# Ddraig.net
KiCad netlist of a schematic drawn in EAGLE
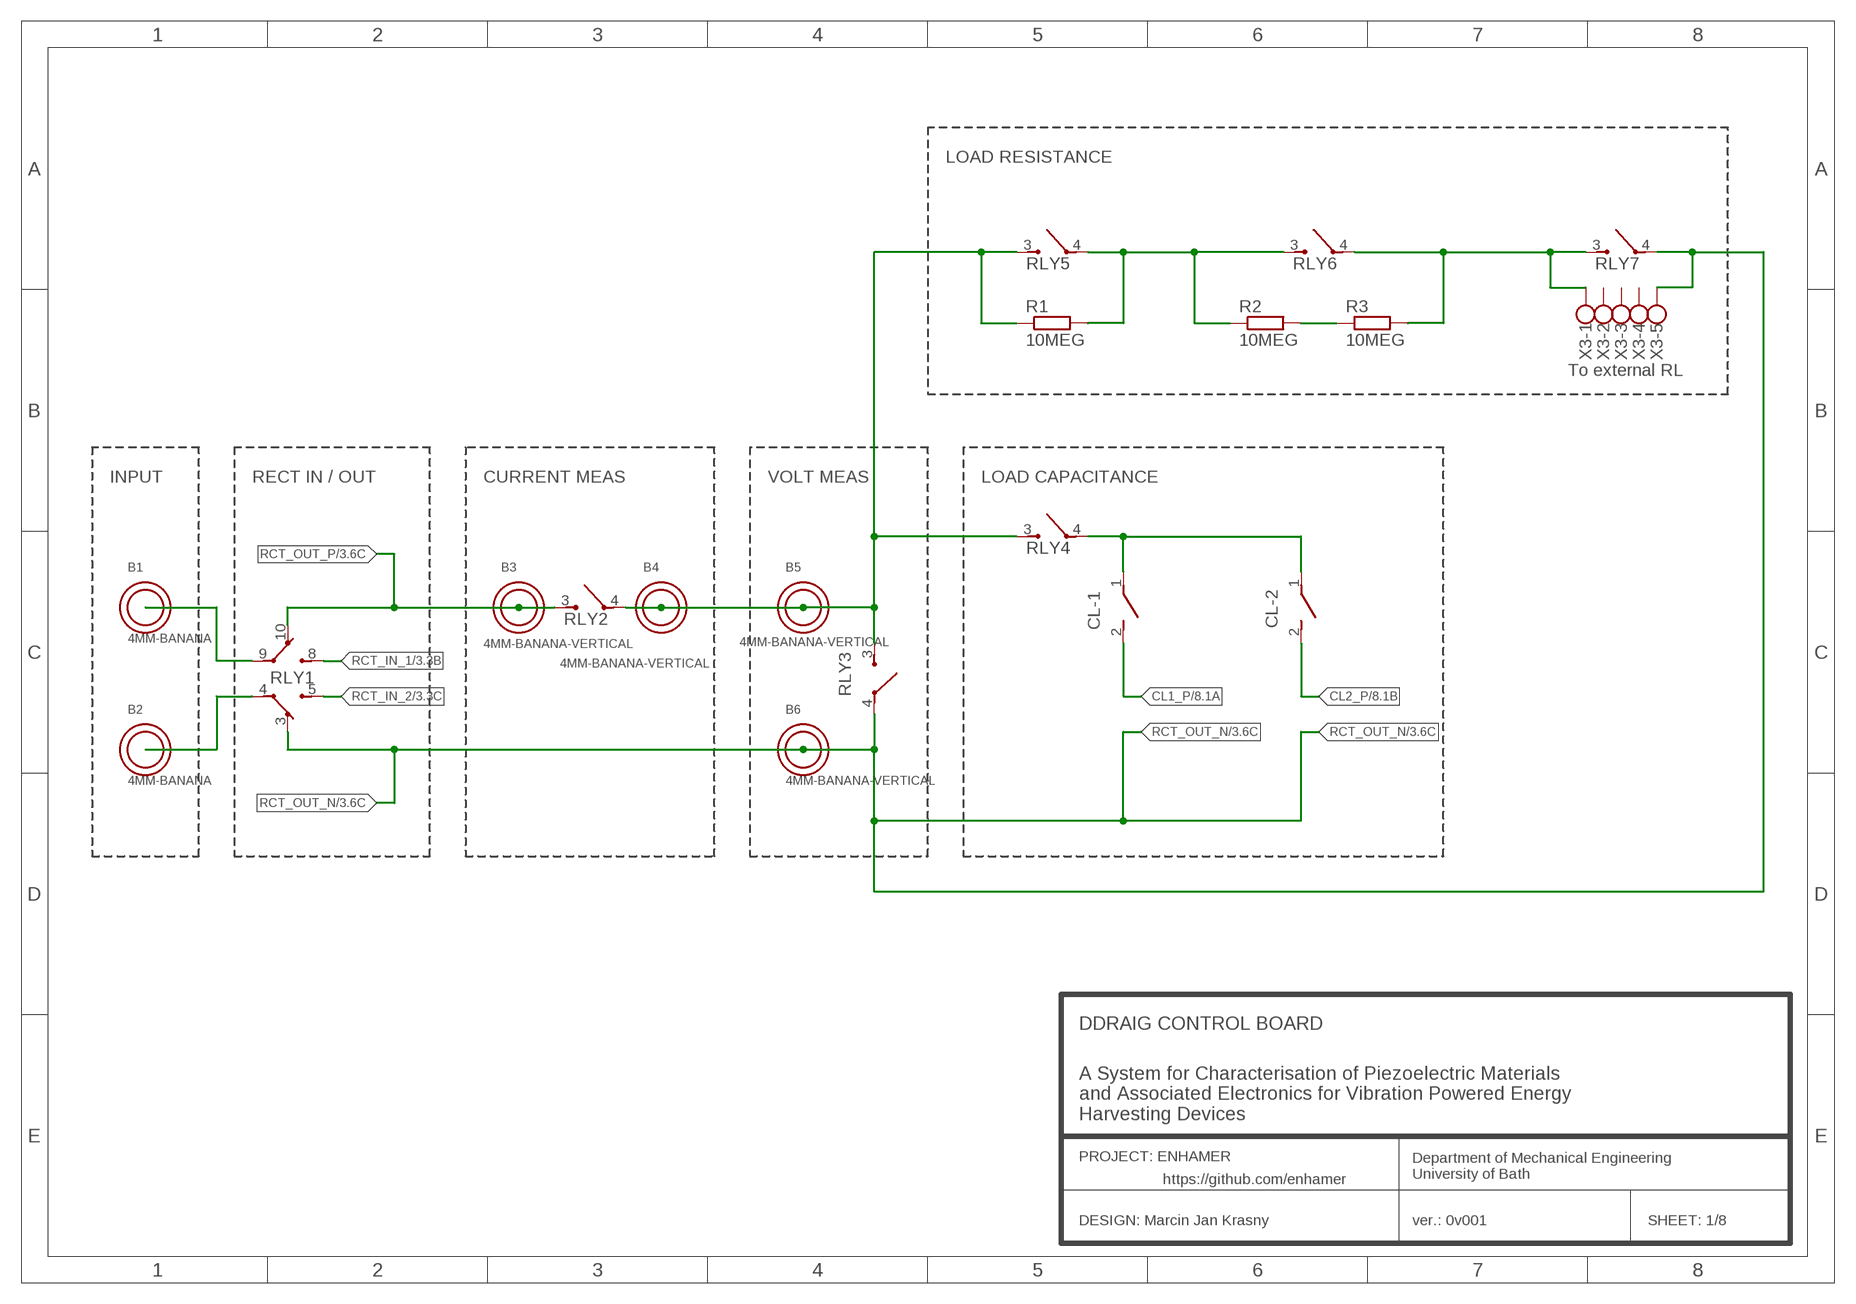
[diagram p0: schematic, sheet 1]
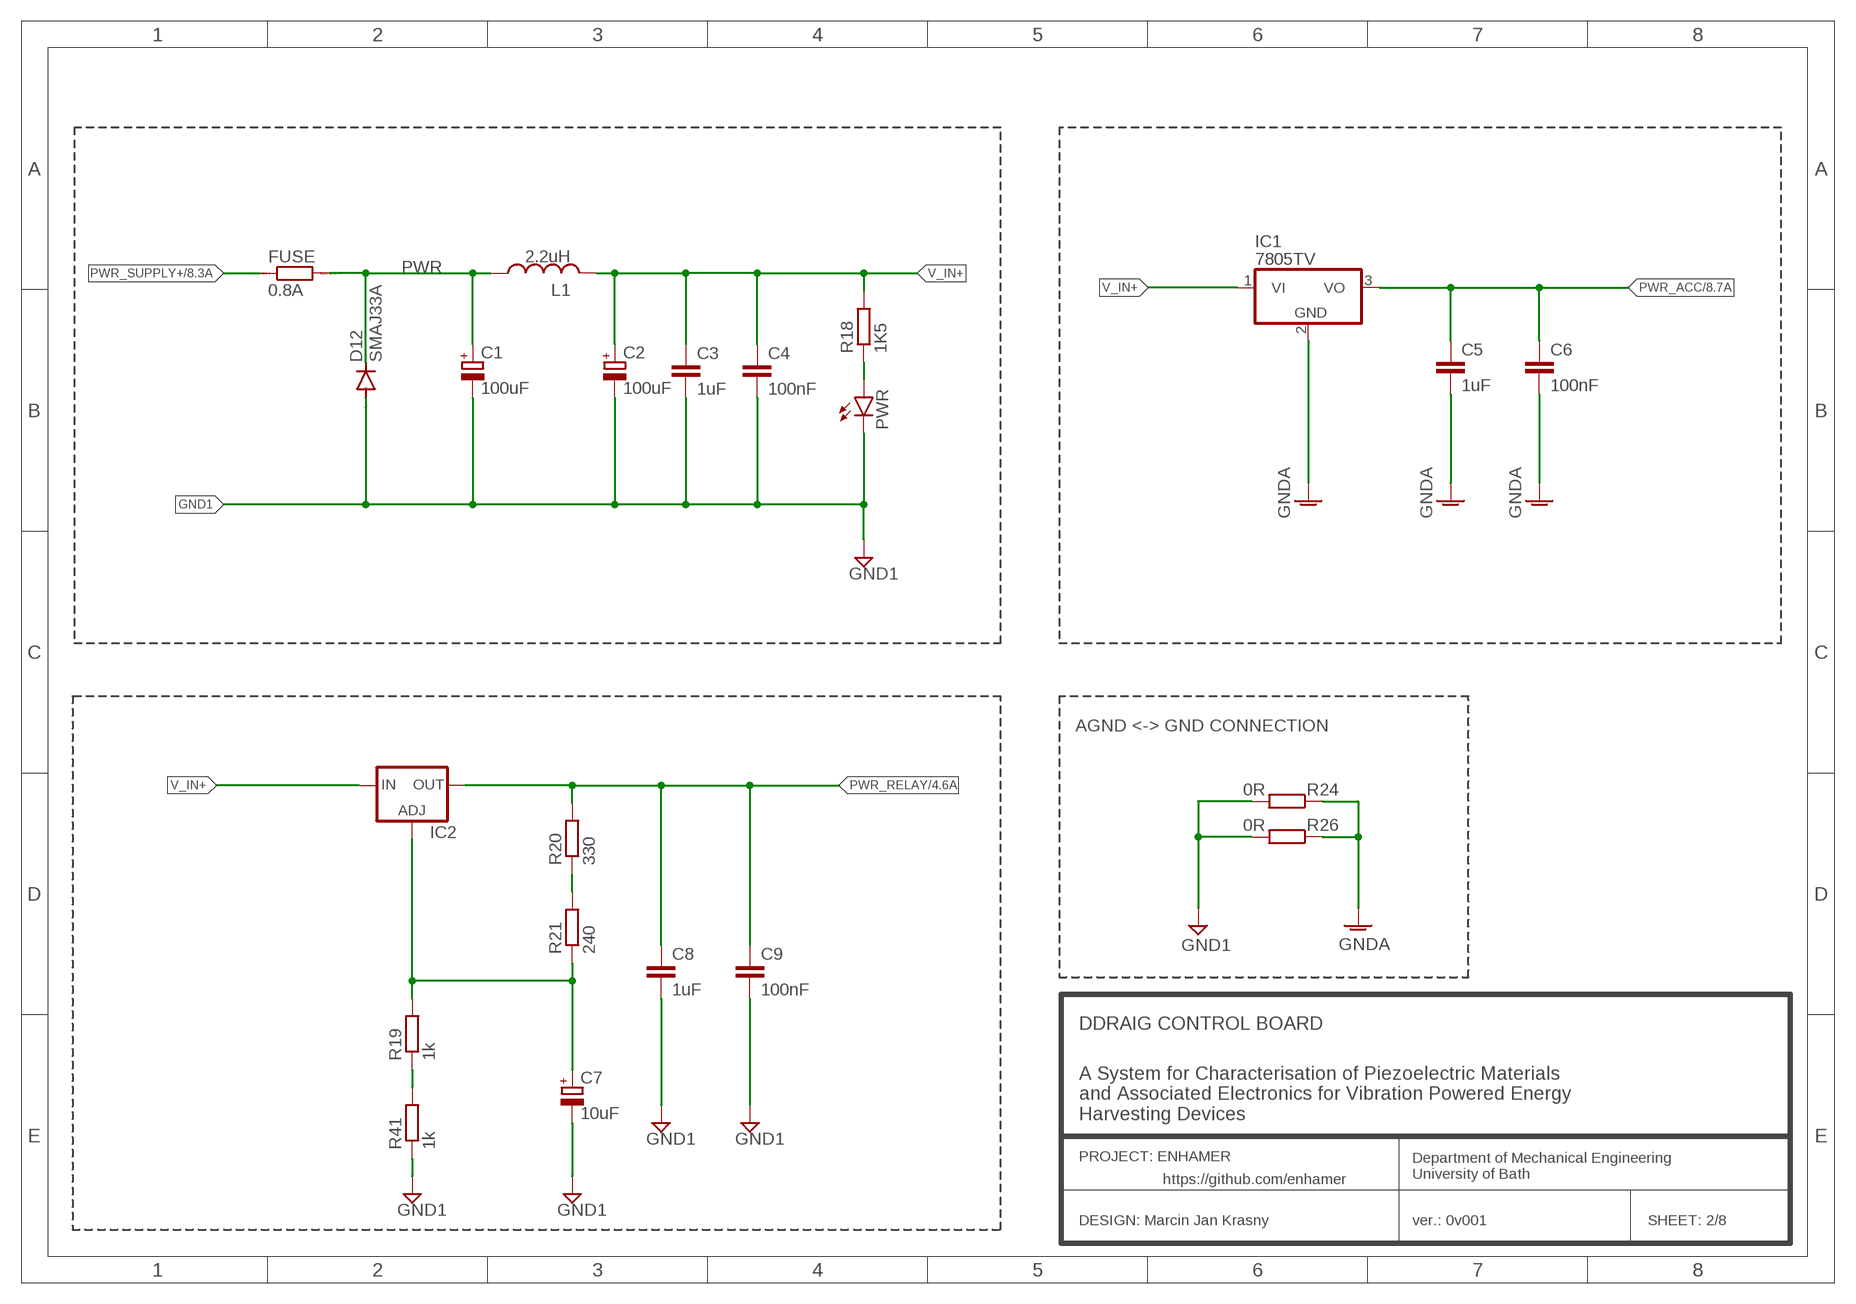
[diagram p1: schematic, sheet 2]
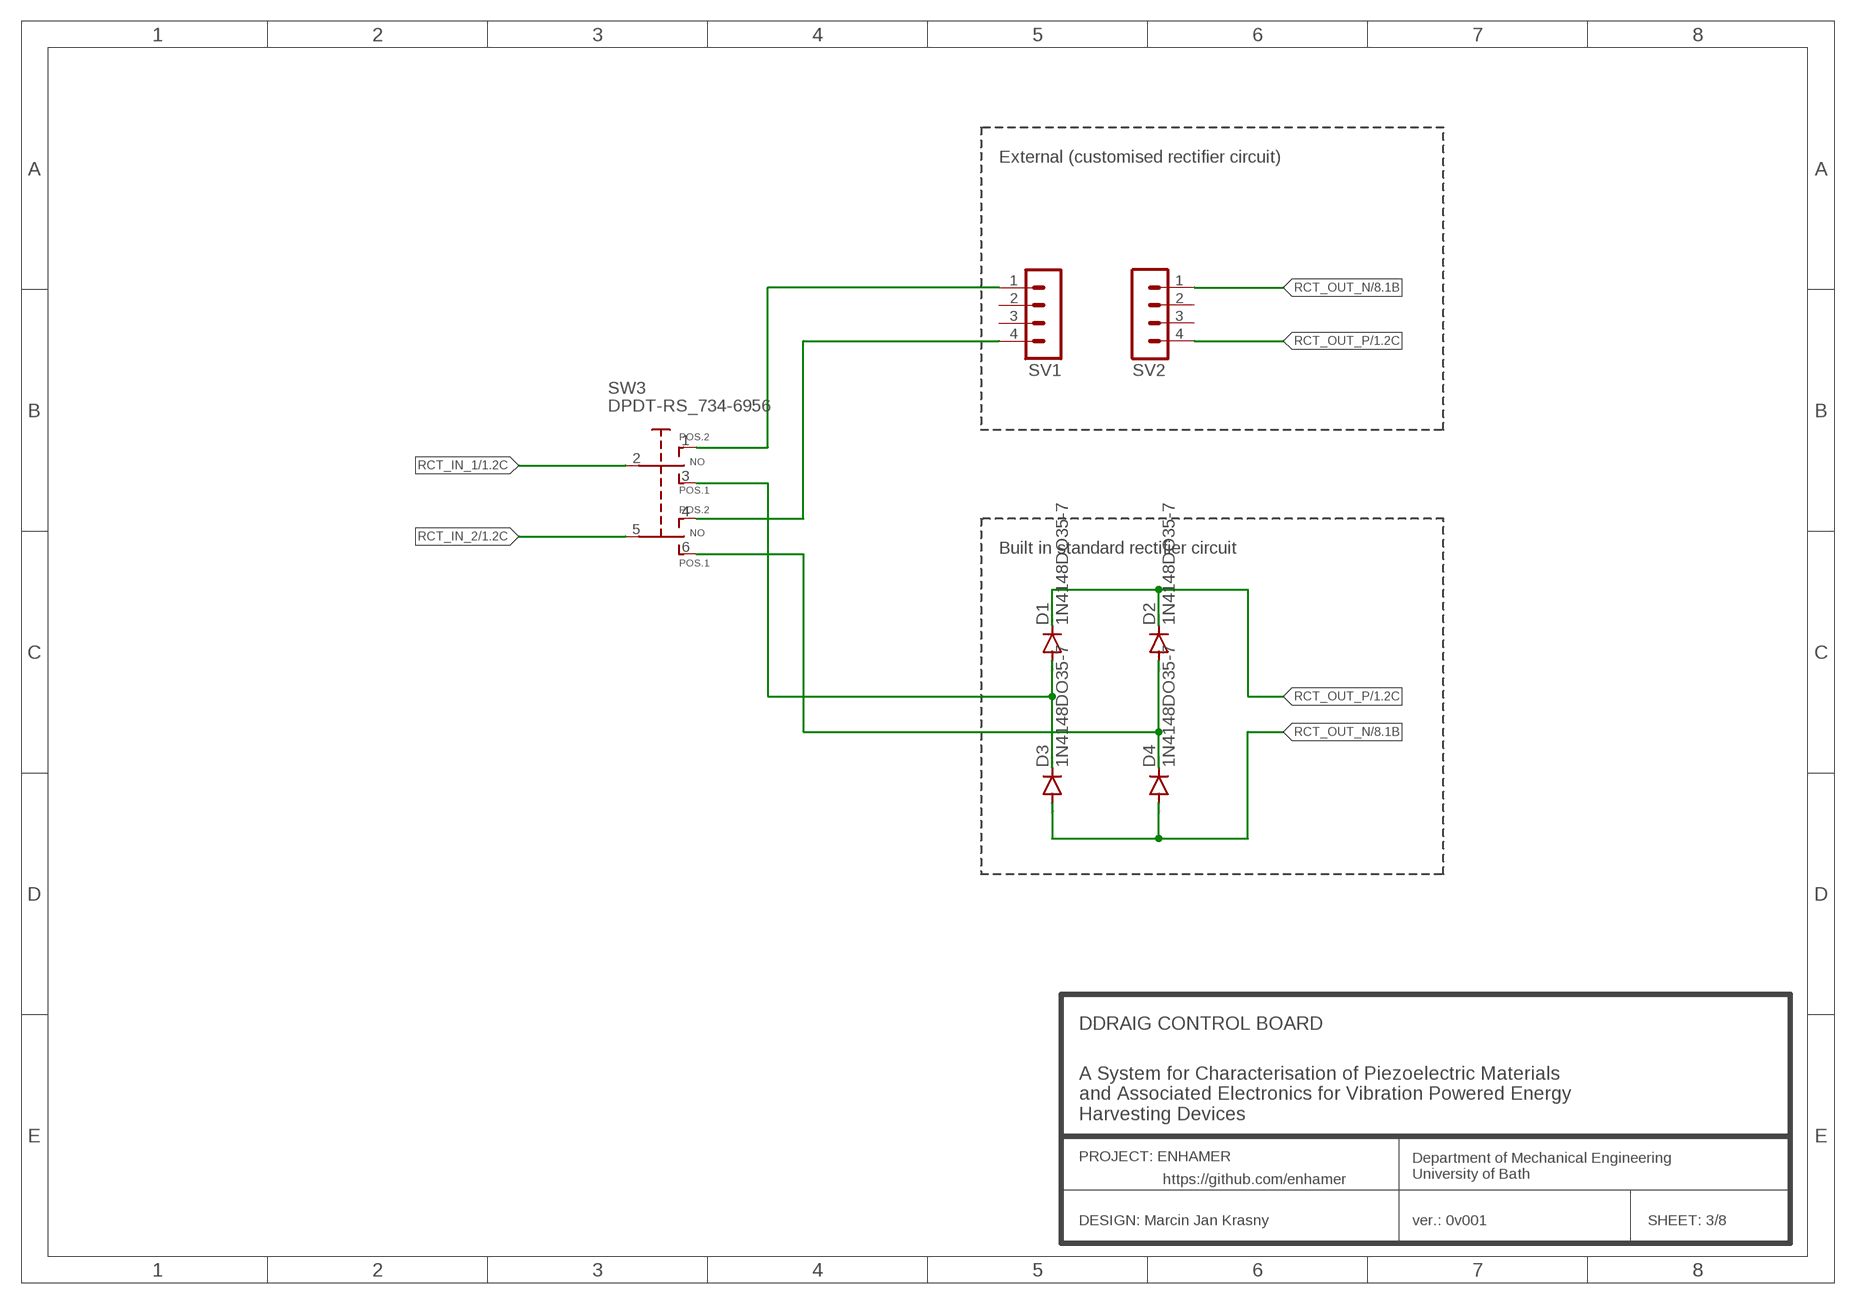
[diagram p2: schematic, sheet 3]
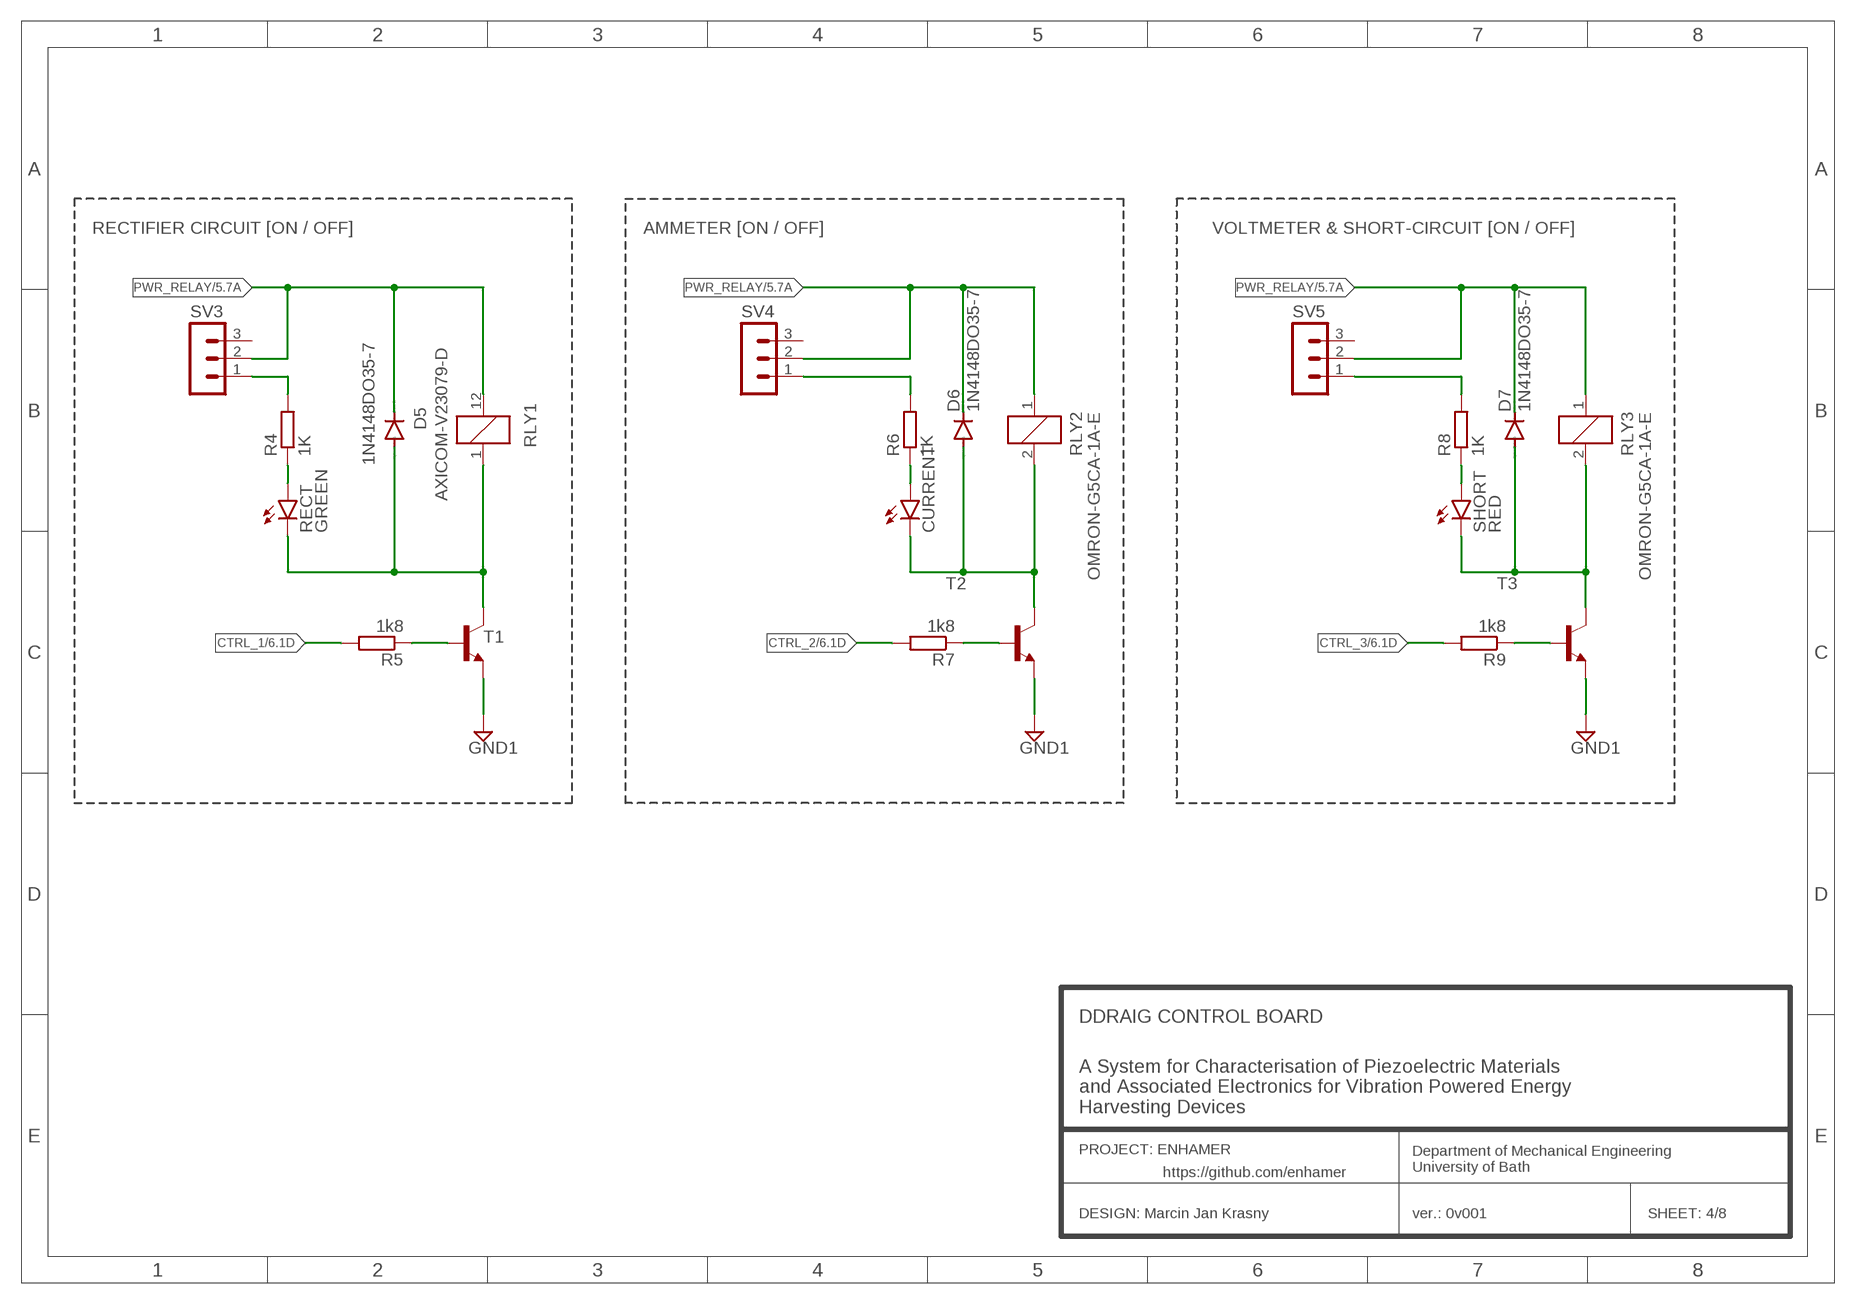
[diagram p3: schematic, sheet 4]
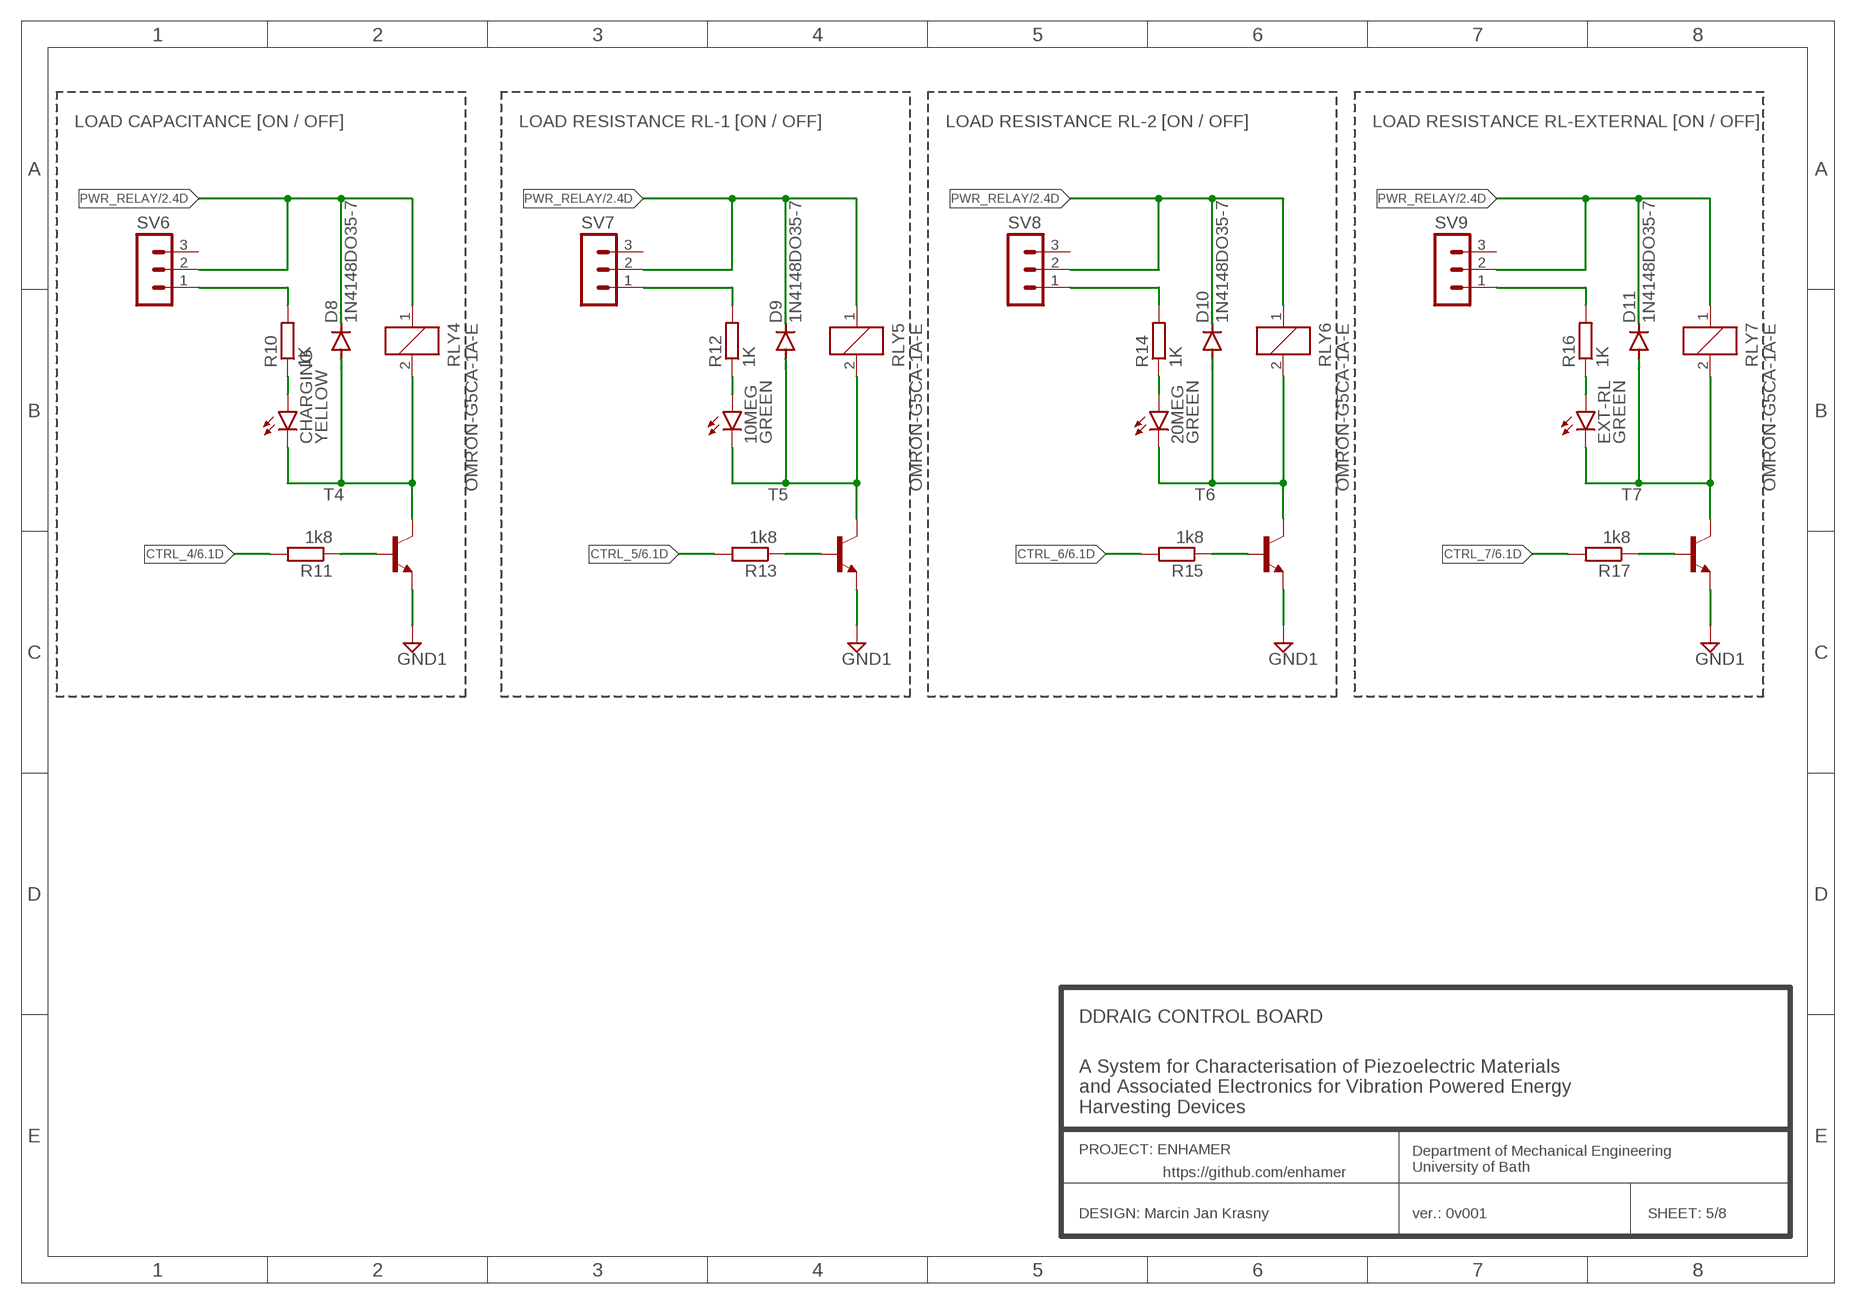
[diagram p4: schematic, sheet 5]
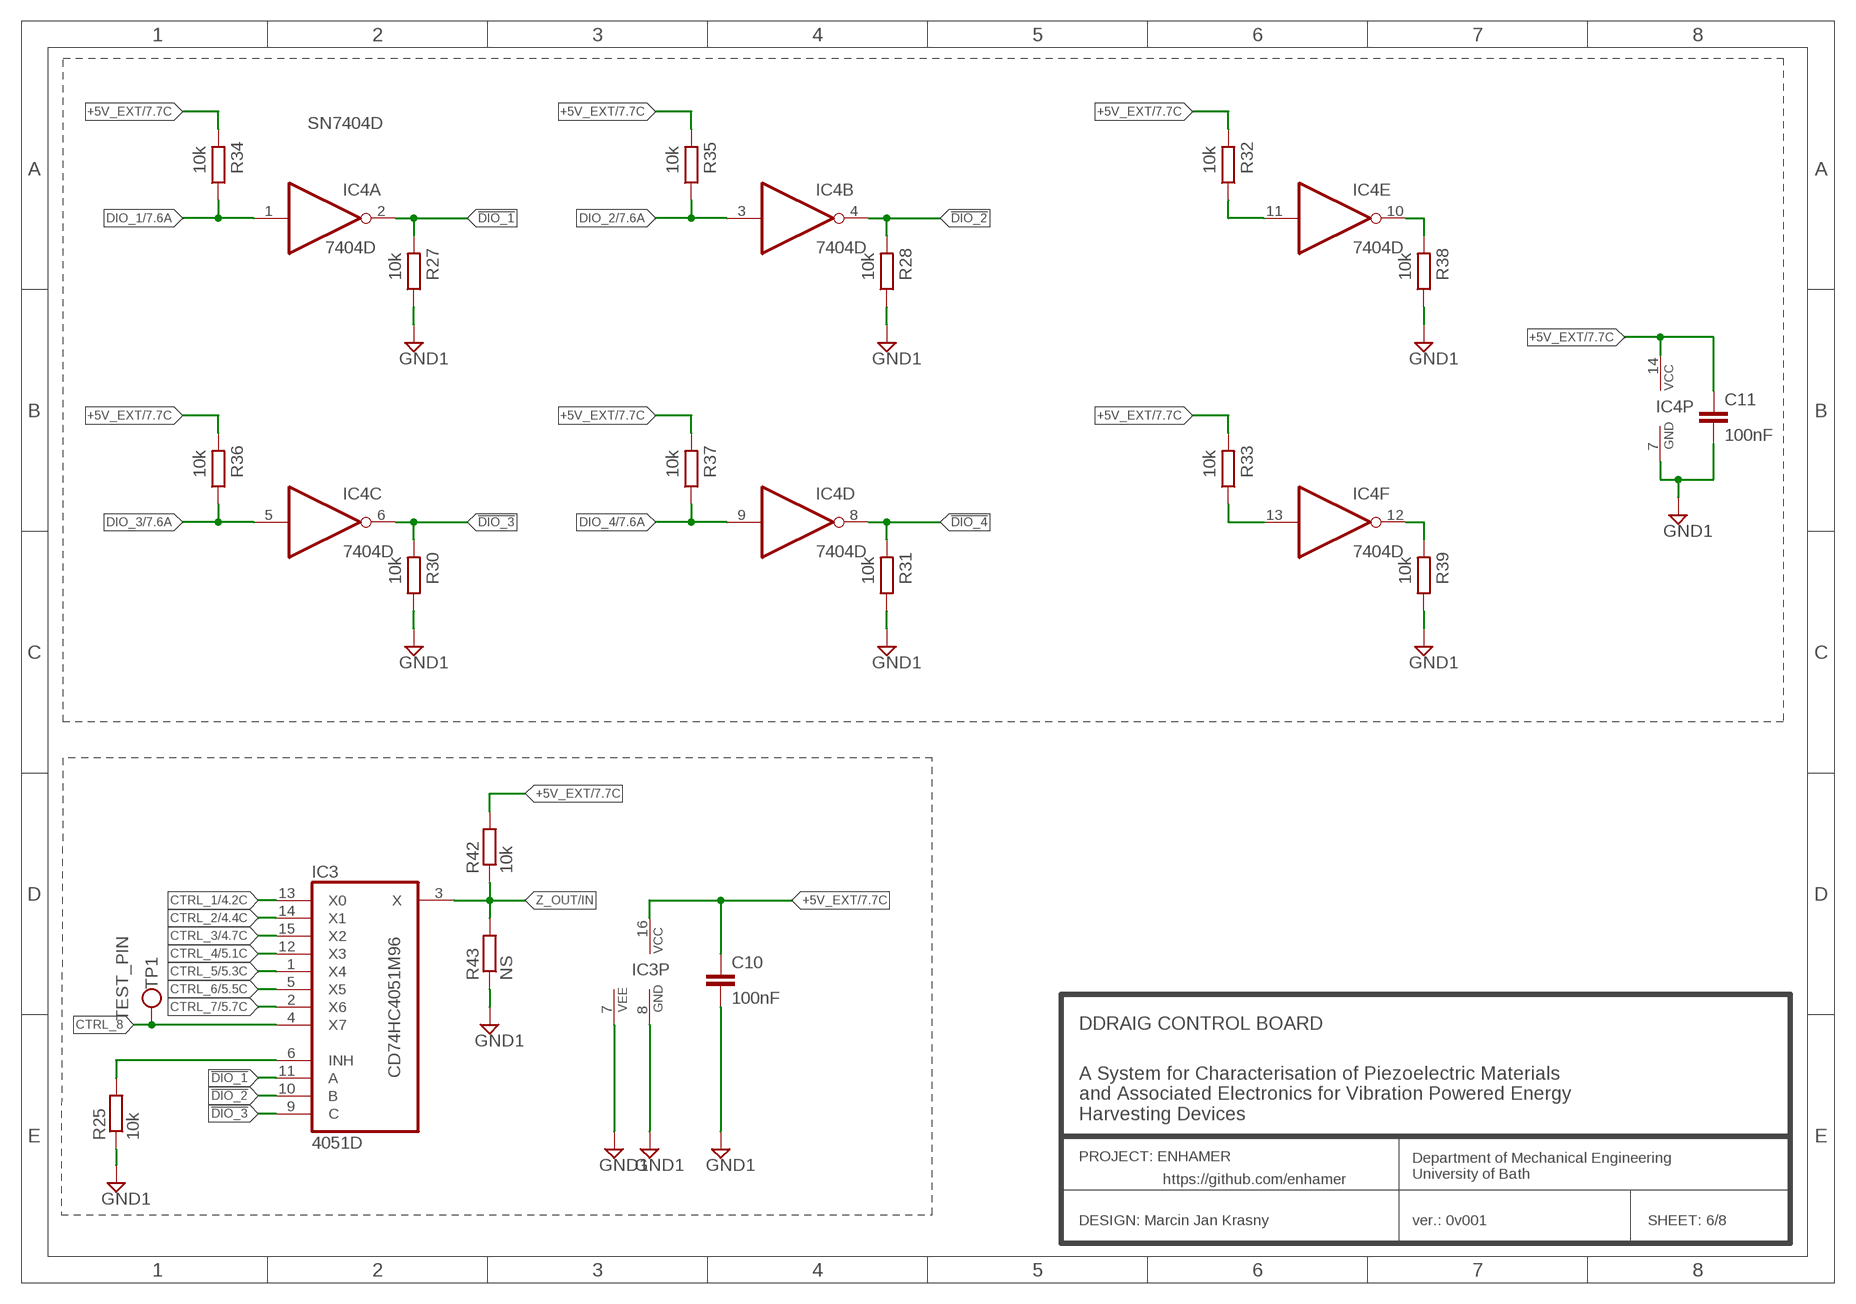
[diagram p5: schematic, sheet 6]
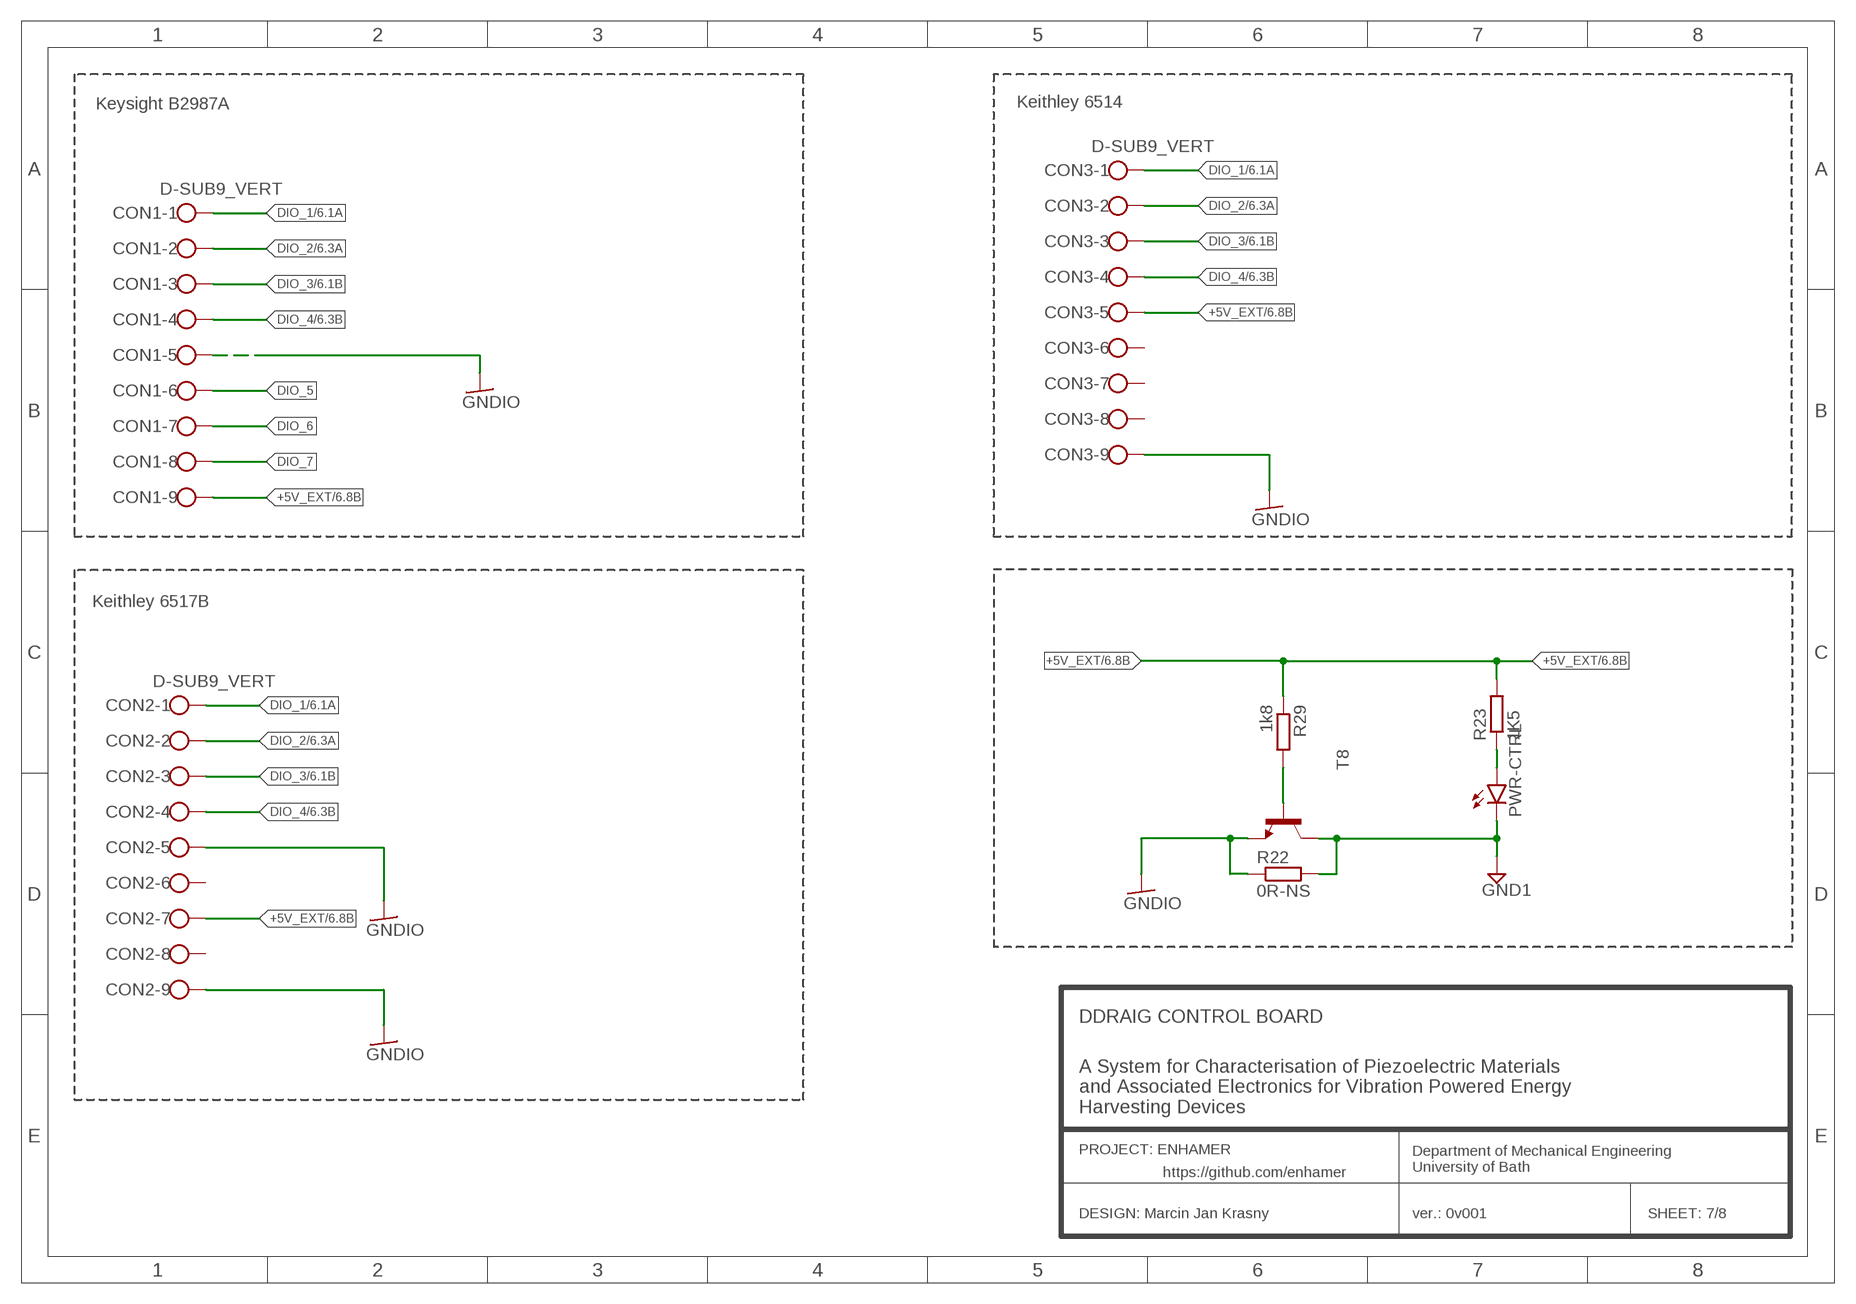
[diagram p6: schematic, sheet 7]
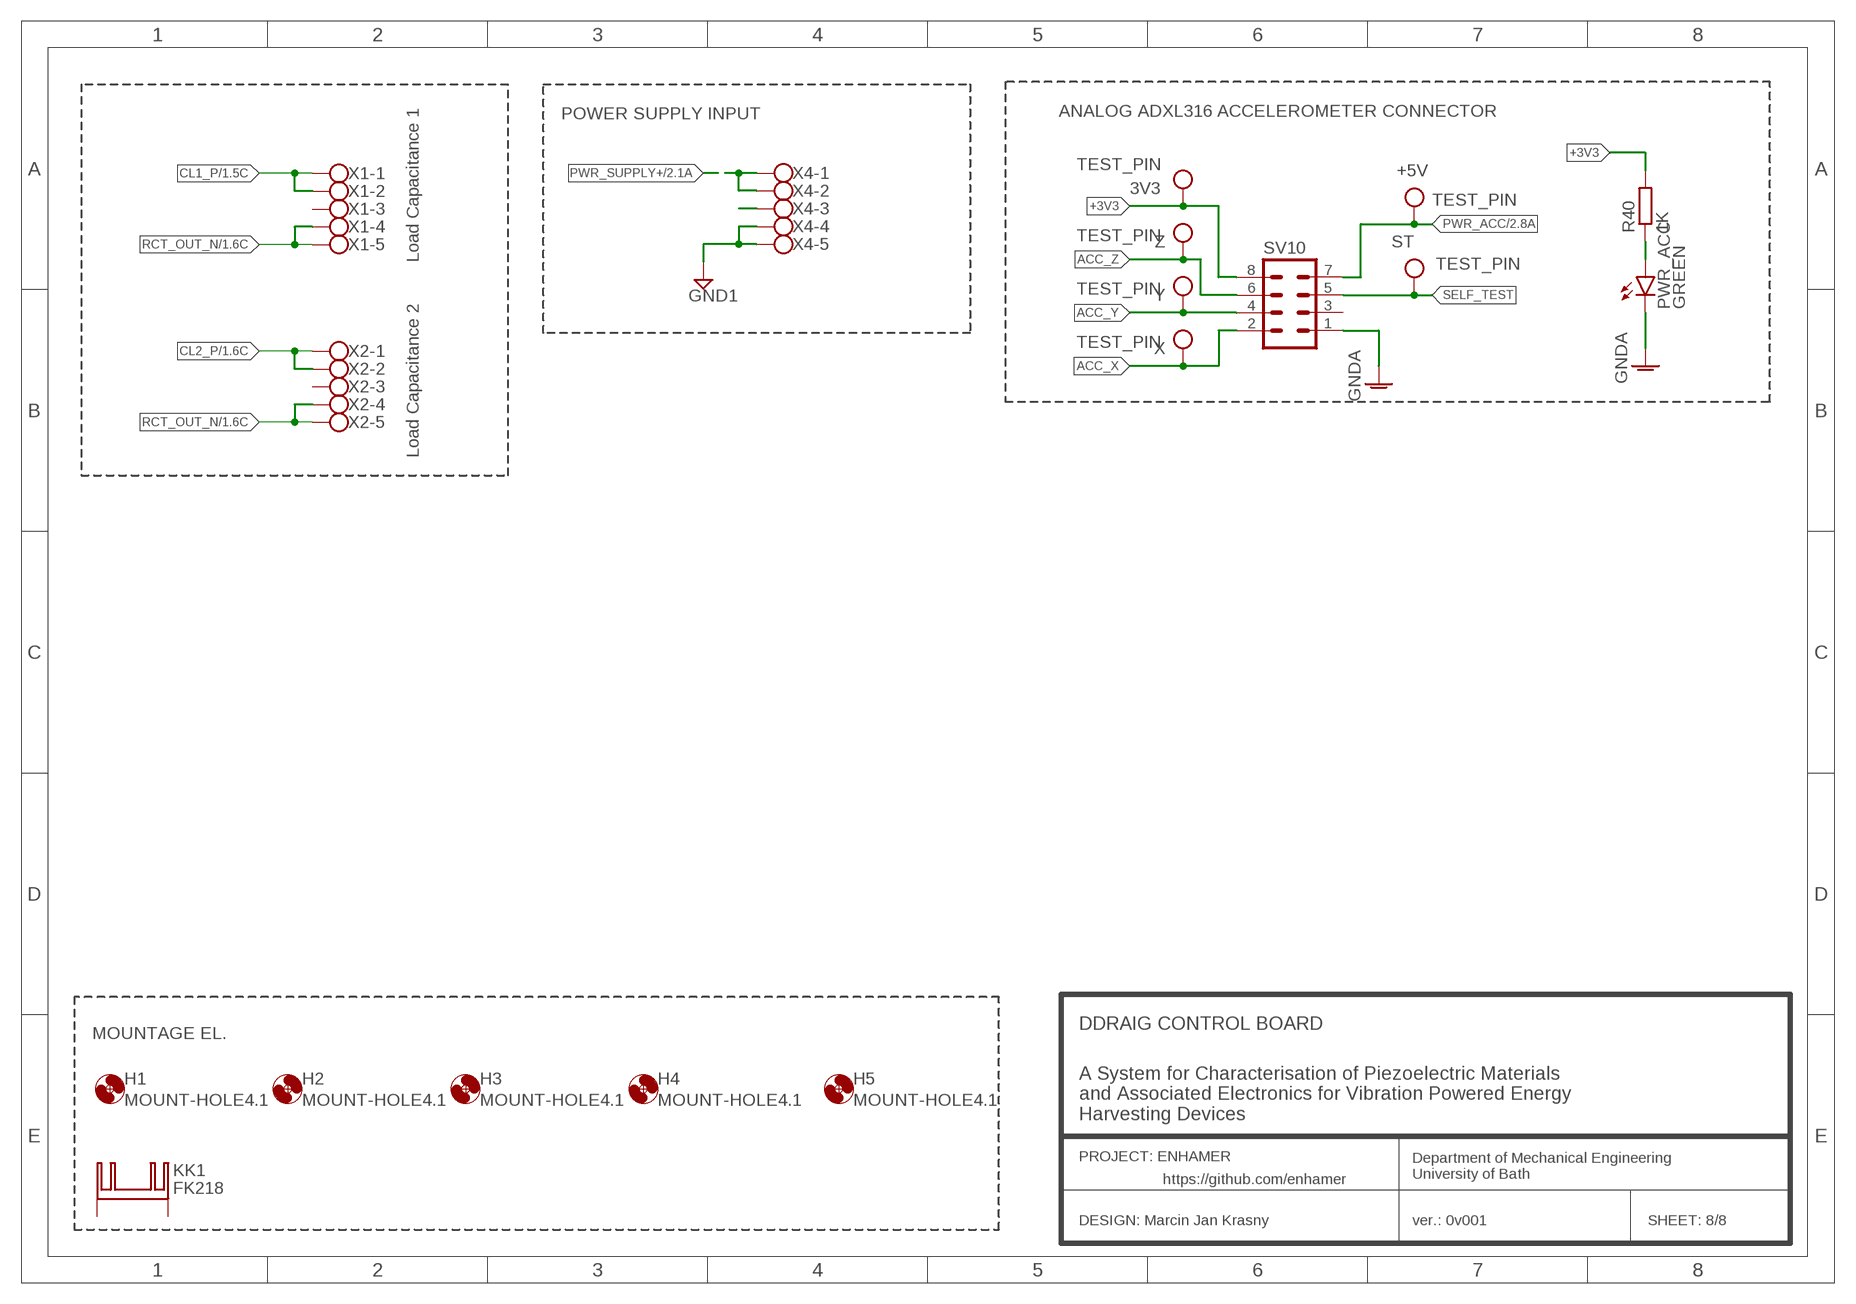
[diagram p7: schematic, sheet 8]

(export (version "E")
  (design (tool "Eeschema 10.0.6"))
  (components
    (comp (ref "D1")
      (value "1N4148DO35-7")
      (footprint "eagle-import:DO35-7")
      (libsource (lib "eagle-import") (part "1N4148DO35-7"))
    )
    (comp (ref "D2")
      (value "1N4148DO35-7")
      (footprint "eagle-import:DO35-7")
      (libsource (lib "eagle-import") (part "1N4148DO35-7"))
    )
    (comp (ref "D3")
      (value "1N4148DO35-7")
      (footprint "eagle-import:DO35-7")
      (libsource (lib "eagle-import") (part "1N4148DO35-7"))
    )
    (comp (ref "D4")
      (value "1N4148DO35-7")
      (footprint "eagle-import:DO35-7")
      (libsource (lib "eagle-import") (part "1N4148DO35-7"))
    )
    (comp (ref "SV1")
      (value "MA04-1")
      (footprint "eagle-import:MA04-1")
      (libsource (lib "eagle-import") (part "MA04-1"))
    )
    (comp (ref "SV2")
      (value "MA04-1")
      (footprint "eagle-import:MA04-1")
      (libsource (lib "eagle-import") (part "MA04-1"))
    )
    (comp (ref "SW3")
      (value "DPDT-RS_734-6956")
      (footprint "eagle-import:DPDT-RS_734-6956")
      (libsource (lib "eagle-import") (part "DPDT-RS_734-6956"))
    )
    (comp (ref "B1")
      (value "4MM-BANANA")
      (footprint "eagle-import:4MM-BANANA-VERTICAL")
      (libsource (lib "eagle-import") (part "4MM-BANANA-VERTICAL"))
    )
    (comp (ref "B2")
      (value "4MM-BANANA")
      (footprint "eagle-import:4MM-BANANA-VERTICAL")
      (libsource (lib "eagle-import") (part "4MM-BANANA-VERTICAL"))
    )
    (comp (ref "B3")
      (value "4MM-BANANA-VERTICAL")
      (footprint "eagle-import:4MM-BANANA-VERTICAL")
      (libsource (lib "eagle-import") (part "4MM-BANANA-VERTICAL"))
    )
    (comp (ref "B4")
      (value "4MM-BANANA-VERTICAL")
      (footprint "eagle-import:4MM-BANANA-VERTICAL")
      (libsource (lib "eagle-import") (part "4MM-BANANA-VERTICAL"))
    )
    (comp (ref "B5")
      (value "4MM-BANANA-VERTICAL")
      (footprint "eagle-import:4MM-BANANA-VERTICAL")
      (libsource (lib "eagle-import") (part "4MM-BANANA-VERTICAL"))
    )
    (comp (ref "B6")
      (value "4MM-BANANA-VERTICAL")
      (footprint "eagle-import:4MM-BANANA-VERTICAL")
      (libsource (lib "eagle-import") (part "4MM-BANANA-VERTICAL"))
    )
    (comp (ref "CL-1")
      (value "DIP_SWITCH_01")
      (footprint "eagle-import:DIP_SWITCH_01")
      (libsource (lib "eagle-import") (part "DIP_SWITCH_01"))
    )
    (comp (ref "CL-2")
      (value "DIP_SWITCH_01")
      (footprint "eagle-import:DIP_SWITCH_01")
      (libsource (lib "eagle-import") (part "DIP_SWITCH_01"))
    )
    (comp (ref "R1")
      (value "10MEG")
      (footprint "eagle-import:R2010")
      (libsource (lib "eagle-import") (part "R-EU_R2010"))
    )
    (comp (ref "R2")
      (value "10MEG")
      (footprint "eagle-import:R2010")
      (libsource (lib "eagle-import") (part "R-EU_R2010"))
    )
    (comp (ref "R3")
      (value "10MEG")
      (footprint "eagle-import:R2010")
      (libsource (lib "eagle-import") (part "R-EU_R2010"))
    )
    (comp (ref "RLY1")
      (value "AXICOM-V23079-D")
      (footprint "eagle-import:AXICOM-V23079-SMT_MONO")
      (libsource (lib "eagle-import") (part "AXICOM-V23079-D"))
    )
    (comp (ref "RLY2")
      (value "OMRON-G5CA-1A-E")
      (footprint "eagle-import:G5CA_MJK")
      (libsource (lib "eagle-import") (part "OMRON-G5CA-1A-E"))
    )
    (comp (ref "RLY3")
      (value "OMRON-G5CA-1A-E")
      (footprint "eagle-import:G5CA_MJK")
      (libsource (lib "eagle-import") (part "OMRON-G5CA-1A-E"))
    )
    (comp (ref "RLY4")
      (value "OMRON-G5CA-1A-E")
      (footprint "eagle-import:G5CA_MJK")
      (libsource (lib "eagle-import") (part "OMRON-G5CA-1A-E"))
    )
    (comp (ref "RLY5")
      (value "OMRON-G5CA-1A-E")
      (footprint "eagle-import:G5CA_MJK")
      (libsource (lib "eagle-import") (part "OMRON-G5CA-1A-E"))
    )
    (comp (ref "RLY6")
      (value "OMRON-G5CA-1A-E")
      (footprint "eagle-import:G5CA_MJK")
      (libsource (lib "eagle-import") (part "OMRON-G5CA-1A-E"))
    )
    (comp (ref "RLY7")
      (value "OMRON-G5CA-1A-E")
      (footprint "eagle-import:G5CA_MJK")
      (libsource (lib "eagle-import") (part "OMRON-G5CA-1A-E"))
    )
    (comp (ref "X3")
      (value "5PIN_CONN_RAST3.5MM")
      (footprint "eagle-import:5PIN_CONN_RAST3.5MM")
      (libsource (lib "eagle-import") (part "5PIN_CONN_RAST3.5MM"))
    )
    (comp (ref "CON1")
      (value "D-SUB9_VERT")
      (footprint "eagle-import:D-SUB9-VERTICAL")
      (libsource (lib "eagle-import") (part "D-SUB9_VERT"))
    )
    (comp (ref "CON2")
      (value "D-SUB9_VERT")
      (footprint "eagle-import:D-SUB9-VERTICAL")
      (libsource (lib "eagle-import") (part "D-SUB9_VERT"))
    )
    (comp (ref "CON3")
      (value "D-SUB9_VERT")
      (footprint "eagle-import:D-SUB9-VERTICAL")
      (libsource (lib "eagle-import") (part "D-SUB9_VERT"))
    )
    (comp (ref "PWR-CTRL")
      (value "LEDSMT1206")
      (footprint "eagle-import:1206")
      (libsource (lib "eagle-import") (part "LEDSMT1206"))
    )
    (comp (ref "R22")
      (value "0R-NS")
      (footprint "eagle-import:R0805")
      (libsource (lib "eagle-import") (part "R-EU_R0805"))
    )
    (comp (ref "R23")
      (value "1K5")
      (footprint "eagle-import:R0805")
      (libsource (lib "eagle-import") (part "R-EU_R0805"))
    )
    (comp (ref "R29")
      (value "1k8")
      (footprint "eagle-import:R0805")
      (libsource (lib "eagle-import") (part "R-EU_R0805"))
    )
    (comp (ref "T8")
      (value "BC337-25-NPN-TO92-CBE")
      (footprint "eagle-import:TO92-CBE")
      (libsource (lib "eagle-import") (part "-NPN-TO92-CBEBC337-25"))
    )
    (comp (ref "CURRENT")
      (value "LEDSMT1206")
      (footprint "eagle-import:1206")
      (libsource (lib "eagle-import") (part "LEDSMT1206"))
    )
    (comp (ref "D5")
      (value "1N4148DO35-7")
      (footprint "eagle-import:DO35-7")
      (libsource (lib "eagle-import") (part "1N4148DO35-7"))
    )
    (comp (ref "D6")
      (value "1N4148DO35-7")
      (footprint "eagle-import:DO35-7")
      (libsource (lib "eagle-import") (part "1N4148DO35-7"))
    )
    (comp (ref "D7")
      (value "1N4148DO35-7")
      (footprint "eagle-import:DO35-7")
      (libsource (lib "eagle-import") (part "1N4148DO35-7"))
    )
    (comp (ref "R4")
      (value "1K")
      (footprint "eagle-import:R0805")
      (libsource (lib "eagle-import") (part "R-EU_R0805"))
    )
    (comp (ref "R5")
      (value "1k8")
      (footprint "eagle-import:R0805")
      (libsource (lib "eagle-import") (part "R-EU_R0805"))
    )
    (comp (ref "R6")
      (value "1K")
      (footprint "eagle-import:R0805")
      (libsource (lib "eagle-import") (part "R-EU_R0805"))
    )
    (comp (ref "R7")
      (value "1k8")
      (footprint "eagle-import:R0805")
      (libsource (lib "eagle-import") (part "R-EU_R0805"))
    )
    (comp (ref "R8")
      (value "1K")
      (footprint "eagle-import:R0805")
      (libsource (lib "eagle-import") (part "R-EU_R0805"))
    )
    (comp (ref "R9")
      (value "1k8")
      (footprint "eagle-import:R0805")
      (libsource (lib "eagle-import") (part "R-EU_R0805"))
    )
    (comp (ref "RECT")
      (value "GREEN")
      (footprint "eagle-import:1206")
      (libsource (lib "eagle-import") (part "LEDSMT1206"))
    )
    (comp (ref "SHORT")
      (value "RED")
      (footprint "eagle-import:1206")
      (libsource (lib "eagle-import") (part "LEDSMT1206"))
    )
    (comp (ref "SV3")
      (value "MA03-1")
      (footprint "eagle-import:MA03-1")
      (libsource (lib "eagle-import") (part "MA03-1"))
    )
    (comp (ref "SV4")
      (value "MA03-1")
      (footprint "eagle-import:MA03-1")
      (libsource (lib "eagle-import") (part "MA03-1"))
    )
    (comp (ref "SV5")
      (value "MA03-1")
      (footprint "eagle-import:MA03-1")
      (libsource (lib "eagle-import") (part "MA03-1"))
    )
    (comp (ref "T1")
      (value "BC337-25-NPN-TO92-CBE")
      (footprint "eagle-import:TO92-CBE")
      (libsource (lib "eagle-import") (part "-NPN-TO92-CBEBC337-25"))
    )
    (comp (ref "T2")
      (value "BC337-25-NPN-TO92-CBE")
      (footprint "eagle-import:TO92-CBE")
      (libsource (lib "eagle-import") (part "-NPN-TO92-CBEBC337-25"))
    )
    (comp (ref "T3")
      (value "BC337-25-NPN-TO92-CBE")
      (footprint "eagle-import:TO92-CBE")
      (libsource (lib "eagle-import") (part "-NPN-TO92-CBEBC337-25"))
    )
    (comp (ref "C1")
      (value "100uF")
      (footprint "eagle-import:PANASONIC-CAPAE660X800N")
      (libsource (lib "eagle-import") (part "C_POL"))
    )
    (comp (ref "C2")
      (value "100uF")
      (footprint "eagle-import:PANASONIC-CAPAE660X800N")
      (libsource (lib "eagle-import") (part "C_POL"))
    )
    (comp (ref "C3")
      (value "1uF")
      (footprint "eagle-import:C0805")
      (libsource (lib "eagle-import") (part "C-EUC0805"))
    )
    (comp (ref "C4")
      (value "100nF")
      (footprint "eagle-import:C0805")
      (libsource (lib "eagle-import") (part "C-EUC0805"))
    )
    (comp (ref "C5")
      (value "1uF")
      (footprint "eagle-import:C0805")
      (libsource (lib "eagle-import") (part "C-EUC0805"))
    )
    (comp (ref "C6")
      (value "100nF")
      (footprint "eagle-import:C0805")
      (libsource (lib "eagle-import") (part "C-EUC0805"))
    )
    (comp (ref "C7")
      (value "10uF")
      (footprint "eagle-import:PANASONIC-CAPAE660X800N")
      (libsource (lib "eagle-import") (part "C_POL"))
    )
    (comp (ref "C8")
      (value "1uF")
      (footprint "eagle-import:C0805")
      (libsource (lib "eagle-import") (part "C-EUC0805"))
    )
    (comp (ref "C9")
      (value "100nF")
      (footprint "eagle-import:C0805")
      (libsource (lib "eagle-import") (part "C-EUC0805"))
    )
    (comp (ref "D12")
      (value "SMAJ33A")
      (footprint "eagle-import:DO-214AC")
      (libsource (lib "eagle-import") (part "DIODE-DO-214AC"))
    )
    (comp (ref "FUSE")
      (value "0.8A")
      (footprint "eagle-import:1206")
      (libsource (lib "eagle-import") (part "R1206"))
    )
    (comp (ref "IC1")
      (value "7805TV")
      (footprint "eagle-import:TO220V")
      (libsource (lib "eagle-import") (part "78TV05"))
    )
    (comp (ref "IC2")
      (value "LM317TS")
      (footprint "eagle-import:317TS")
      (libsource (lib "eagle-import") (part "LM317TS"))
    )
    (comp (ref "L1")
      (value "2.2uH")
      (footprint "eagle-import:0805")
      (libsource (lib "eagle-import") (part "L0805_[2016_METRIC]"))
    )
    (comp (ref "PWR")
      (value "LEDSMT1206")
      (footprint "eagle-import:1206")
      (libsource (lib "eagle-import") (part "LEDSMT1206"))
    )
    (comp (ref "R18")
      (value "1K5")
      (footprint "eagle-import:R0805")
      (libsource (lib "eagle-import") (part "R-EU_R0805"))
    )
    (comp (ref "R19")
      (value "1k")
      (footprint "eagle-import:R0805")
      (libsource (lib "eagle-import") (part "R-EU_R0805"))
    )
    (comp (ref "R20")
      (value "330")
      (footprint "eagle-import:R0805")
      (libsource (lib "eagle-import") (part "R-EU_R0805"))
    )
    (comp (ref "R21")
      (value "240")
      (footprint "eagle-import:R0805")
      (libsource (lib "eagle-import") (part "R-EU_R0805"))
    )
    (comp (ref "R24")
      (value "0R")
      (footprint "eagle-import:R0805")
      (libsource (lib "eagle-import") (part "R-EU_R0805"))
    )
    (comp (ref "R26")
      (value "0R")
      (footprint "eagle-import:R0805")
      (libsource (lib "eagle-import") (part "R-EU_R0805"))
    )
    (comp (ref "R41")
      (value "1k")
      (footprint "eagle-import:R0805")
      (libsource (lib "eagle-import") (part "R-EU_R0805"))
    )
    (comp (ref "+5V")
      (value "TEST_PIN")
      (footprint "eagle-import:1-TEST_PIN")
      (libsource (lib "eagle-import") (part "TEST_PIN"))
    )
    (comp (ref "3V3")
      (value "TEST_PIN")
      (footprint "eagle-import:1-TEST_PIN")
      (libsource (lib "eagle-import") (part "TEST_PIN"))
    )
    (comp (ref "H1")
      (value "MOUNT-HOLE4.1")
      (footprint "eagle-import:4,1")
      (libsource (lib "eagle-import") (part "MOUNT-HOLE4.1"))
    )
    (comp (ref "H2")
      (value "MOUNT-HOLE4.1")
      (footprint "eagle-import:4,1")
      (libsource (lib "eagle-import") (part "MOUNT-HOLE4.1"))
    )
    (comp (ref "H3")
      (value "MOUNT-HOLE4.1")
      (footprint "eagle-import:4,1")
      (libsource (lib "eagle-import") (part "MOUNT-HOLE4.1"))
    )
    (comp (ref "H4")
      (value "MOUNT-HOLE4.1")
      (footprint "eagle-import:4,1")
      (libsource (lib "eagle-import") (part "MOUNT-HOLE4.1"))
    )
    (comp (ref "H5")
      (value "MOUNT-HOLE4.1")
      (footprint "eagle-import:4,1")
      (libsource (lib "eagle-import") (part "MOUNT-HOLE4.1"))
    )
    (comp (ref "KK1")
      (value "FK218")
      (footprint "eagle-import:FK218")
      (libsource (lib "eagle-import") (part "FK218"))
    )
    (comp (ref "PWR_ACC")
      (value "GREEN")
      (footprint "eagle-import:1206")
      (libsource (lib "eagle-import") (part "LEDSMT1206"))
    )
    (comp (ref "R40")
      (value "1K")
      (footprint "eagle-import:R0805")
      (libsource (lib "eagle-import") (part "R-EU_R0805"))
    )
    (comp (ref "ST")
      (value "TEST_PIN")
      (footprint "eagle-import:1-TEST_PIN")
      (libsource (lib "eagle-import") (part "TEST_PIN"))
    )
    (comp (ref "SV10")
      (value "MA04-2")
      (footprint "eagle-import:MA04-2")
      (libsource (lib "eagle-import") (part "MA04-2"))
    )
    (comp (ref "X")
      (value "TEST_PIN")
      (footprint "eagle-import:1-TEST_PIN")
      (libsource (lib "eagle-import") (part "TEST_PIN"))
    )
    (comp (ref "X1")
      (value "5PIN_CONN_RAST3.5MM")
      (footprint "eagle-import:5PIN_CONN_RAST3.5MM")
      (libsource (lib "eagle-import") (part "5PIN_CONN_RAST3.5MM"))
    )
    (comp (ref "X2")
      (value "5PIN_CONN_RAST3.5MM")
      (footprint "eagle-import:5PIN_CONN_RAST3.5MM")
      (libsource (lib "eagle-import") (part "5PIN_CONN_RAST3.5MM"))
    )
    (comp (ref "X4")
      (value "5PIN_CONN_RAST3.5MM")
      (footprint "eagle-import:5PIN_CONN_RAST3.5MM")
      (libsource (lib "eagle-import") (part "5PIN_CONN_RAST3.5MM"))
    )
    (comp (ref "Y")
      (value "TEST_PIN")
      (footprint "eagle-import:1-TEST_PIN")
      (libsource (lib "eagle-import") (part "TEST_PIN"))
    )
    (comp (ref "Z")
      (value "TEST_PIN")
      (footprint "eagle-import:1-TEST_PIN")
      (libsource (lib "eagle-import") (part "TEST_PIN"))
    )
    (comp (ref "10MEG")
      (value "GREEN")
      (footprint "eagle-import:1206")
      (libsource (lib "eagle-import") (part "LEDSMT1206"))
    )
    (comp (ref "20MEG")
      (value "GREEN")
      (footprint "eagle-import:1206")
      (libsource (lib "eagle-import") (part "LEDSMT1206"))
    )
    (comp (ref "CHARGING")
      (value "YELLOW")
      (footprint "eagle-import:1206")
      (libsource (lib "eagle-import") (part "LEDSMT1206"))
    )
    (comp (ref "D8")
      (value "1N4148DO35-7")
      (footprint "eagle-import:DO35-7")
      (libsource (lib "eagle-import") (part "1N4148DO35-7"))
    )
    (comp (ref "D9")
      (value "1N4148DO35-7")
      (footprint "eagle-import:DO35-7")
      (libsource (lib "eagle-import") (part "1N4148DO35-7"))
    )
    (comp (ref "D10")
      (value "1N4148DO35-7")
      (footprint "eagle-import:DO35-7")
      (libsource (lib "eagle-import") (part "1N4148DO35-7"))
    )
    (comp (ref "D11")
      (value "1N4148DO35-7")
      (footprint "eagle-import:DO35-7")
      (libsource (lib "eagle-import") (part "1N4148DO35-7"))
    )
    (comp (ref "EXT-RL")
      (value "GREEN")
      (footprint "eagle-import:1206")
      (libsource (lib "eagle-import") (part "LEDSMT1206"))
    )
    (comp (ref "R10")
      (value "1K")
      (footprint "eagle-import:R0805")
      (libsource (lib "eagle-import") (part "R-EU_R0805"))
    )
    (comp (ref "R11")
      (value "1k8")
      (footprint "eagle-import:R0805")
      (libsource (lib "eagle-import") (part "R-EU_R0805"))
    )
    (comp (ref "R12")
      (value "1K")
      (footprint "eagle-import:R0805")
      (libsource (lib "eagle-import") (part "R-EU_R0805"))
    )
    (comp (ref "R13")
      (value "1k8")
      (footprint "eagle-import:R0805")
      (libsource (lib "eagle-import") (part "R-EU_R0805"))
    )
    (comp (ref "R14")
      (value "1K")
      (footprint "eagle-import:R0805")
      (libsource (lib "eagle-import") (part "R-EU_R0805"))
    )
    (comp (ref "R15")
      (value "1k8")
      (footprint "eagle-import:R0805")
      (libsource (lib "eagle-import") (part "R-EU_R0805"))
    )
    (comp (ref "R16")
      (value "1K")
      (footprint "eagle-import:R0805")
      (libsource (lib "eagle-import") (part "R-EU_R0805"))
    )
    (comp (ref "R17")
      (value "1k8")
      (footprint "eagle-import:R0805")
      (libsource (lib "eagle-import") (part "R-EU_R0805"))
    )
    (comp (ref "SV6")
      (value "MA03-1")
      (footprint "eagle-import:MA03-1")
      (libsource (lib "eagle-import") (part "MA03-1"))
    )
    (comp (ref "SV7")
      (value "MA03-1")
      (footprint "eagle-import:MA03-1")
      (libsource (lib "eagle-import") (part "MA03-1"))
    )
    (comp (ref "SV8")
      (value "MA03-1")
      (footprint "eagle-import:MA03-1")
      (libsource (lib "eagle-import") (part "MA03-1"))
    )
    (comp (ref "SV9")
      (value "MA03-1")
      (footprint "eagle-import:MA03-1")
      (libsource (lib "eagle-import") (part "MA03-1"))
    )
    (comp (ref "T4")
      (value "BC337-25-NPN-TO92-CBE")
      (footprint "eagle-import:TO92-CBE")
      (libsource (lib "eagle-import") (part "-NPN-TO92-CBEBC337-25"))
    )
    (comp (ref "T5")
      (value "BC337-25-NPN-TO92-CBE")
      (footprint "eagle-import:TO92-CBE")
      (libsource (lib "eagle-import") (part "-NPN-TO92-CBEBC337-25"))
    )
    (comp (ref "T6")
      (value "BC337-25-NPN-TO92-CBE")
      (footprint "eagle-import:TO92-CBE")
      (libsource (lib "eagle-import") (part "-NPN-TO92-CBEBC337-25"))
    )
    (comp (ref "T7")
      (value "BC337-25-NPN-TO92-CBE")
      (footprint "eagle-import:TO92-CBE")
      (libsource (lib "eagle-import") (part "-NPN-TO92-CBEBC337-25"))
    )
    (comp (ref "C10")
      (value "100nF")
      (footprint "eagle-import:C0805")
      (libsource (lib "eagle-import") (part "C-EUC0805"))
    )
    (comp (ref "C11")
      (value "100nF")
      (footprint "eagle-import:C0805")
      (libsource (lib "eagle-import") (part "C-EUC0805"))
    )
    (comp (ref "IC3")
      (value "4051D")
      (footprint "eagle-import:SO16")
      (libsource (lib "eagle-import") (part "4051D"))
    )
    (comp (ref "IC4")
      (value "7404D")
      (footprint "eagle-import:SO14")
      (libsource (lib "eagle-import") (part "7404D"))
    )
    (comp (ref "R25")
      (value "10k")
      (footprint "eagle-import:R0805")
      (libsource (lib "eagle-import") (part "R-EU_R0805"))
    )
    (comp (ref "R27")
      (value "10k")
      (footprint "eagle-import:R0805")
      (libsource (lib "eagle-import") (part "R-EU_R0805"))
    )
    (comp (ref "R28")
      (value "10k")
      (footprint "eagle-import:R0805")
      (libsource (lib "eagle-import") (part "R-EU_R0805"))
    )
    (comp (ref "R30")
      (value "10k")
      (footprint "eagle-import:R0805")
      (libsource (lib "eagle-import") (part "R-EU_R0805"))
    )
    (comp (ref "R31")
      (value "10k")
      (footprint "eagle-import:R0805")
      (libsource (lib "eagle-import") (part "R-EU_R0805"))
    )
    (comp (ref "R32")
      (value "10k")
      (footprint "eagle-import:R0805")
      (libsource (lib "eagle-import") (part "R-EU_R0805"))
    )
    (comp (ref "R33")
      (value "10k")
      (footprint "eagle-import:R0805")
      (libsource (lib "eagle-import") (part "R-EU_R0805"))
    )
    (comp (ref "R34")
      (value "10k")
      (footprint "eagle-import:R0805")
      (libsource (lib "eagle-import") (part "R-EU_R0805"))
    )
    (comp (ref "R35")
      (value "10k")
      (footprint "eagle-import:R0805")
      (libsource (lib "eagle-import") (part "R-EU_R0805"))
    )
    (comp (ref "R36")
      (value "10k")
      (footprint "eagle-import:R0805")
      (libsource (lib "eagle-import") (part "R-EU_R0805"))
    )
    (comp (ref "R37")
      (value "10k")
      (footprint "eagle-import:R0805")
      (libsource (lib "eagle-import") (part "R-EU_R0805"))
    )
    (comp (ref "R38")
      (value "10k")
      (footprint "eagle-import:R0805")
      (libsource (lib "eagle-import") (part "R-EU_R0805"))
    )
    (comp (ref "R39")
      (value "10k")
      (footprint "eagle-import:R0805")
      (libsource (lib "eagle-import") (part "R-EU_R0805"))
    )
    (comp (ref "R42")
      (value "10k")
      (footprint "eagle-import:R0805")
      (libsource (lib "eagle-import") (part "R-EU_R0805"))
    )
    (comp (ref "R43")
      (value "NS")
      (footprint "eagle-import:R0805")
      (libsource (lib "eagle-import") (part "R-EU_R0805"))
    )
    (comp (ref "TP1")
      (value "TEST_PIN")
      (footprint "eagle-import:1-TEST_PIN")
      (libsource (lib "eagle-import") (part "TEST_PIN"))
    )
  )
  (nets
    (net (code "1") (name "+3V3") (class "Default")
      (node (ref "3V3") (pin "1") (pinfunction "KL_1") (pintype "passive"))
      (node (ref "R40") (pin "2") (pinfunction "2_2") (pintype "passive"))
      (node (ref "SV10") (pin "8") (pinfunction "8_8") (pintype "passive"))
    )
    (net (code "2") (name "+5V_EXT") (class "Default")
      (node (ref "C10") (pin "1") (pinfunction "1_1") (pintype "passive"))
      (node (ref "C11") (pin "1") (pinfunction "1_1") (pintype "passive"))
      (node (ref "CON1") (pin "9") (pinfunction "KL_9") (pintype "passive"))
      (node (ref "CON2") (pin "7") (pinfunction "KL_7") (pintype "passive"))
      (node (ref "CON3") (pin "5") (pinfunction "KL_5") (pintype "passive"))
      (node (ref "IC3") (pin "16") (pinfunction "VCC_16") (pintype "power_in"))
      (node (ref "IC4") (pin "14") (pinfunction "VCC_14") (pintype "power_in"))
      (node (ref "R23") (pin "2") (pinfunction "2_2") (pintype "passive"))
      (node (ref "R29") (pin "1") (pinfunction "1_1") (pintype "passive"))
      (node (ref "R32") (pin "2") (pinfunction "2_2") (pintype "passive"))
      (node (ref "R33") (pin "2") (pinfunction "2_2") (pintype "passive"))
      (node (ref "R34") (pin "2") (pinfunction "2_2") (pintype "passive"))
      (node (ref "R35") (pin "2") (pinfunction "2_2") (pintype "passive"))
      (node (ref "R36") (pin "2") (pinfunction "2_2") (pintype "passive"))
      (node (ref "R37") (pin "2") (pinfunction "2_2") (pintype "passive"))
      (node (ref "R42") (pin "2") (pinfunction "2_2") (pintype "passive"))
    )
    (net (code "3") (name "ACC_X") (class "Default")
      (node (ref "SV10") (pin "2") (pinfunction "2_2") (pintype "passive"))
      (node (ref "X") (pin "1") (pinfunction "KL_1") (pintype "passive"))
    )
    (net (code "4") (name "ACC_Y") (class "Default")
      (node (ref "SV10") (pin "4") (pinfunction "4_4") (pintype "passive"))
      (node (ref "Y") (pin "1") (pinfunction "KL_1") (pintype "passive"))
    )
    (net (code "5") (name "ACC_Z") (class "Default")
      (node (ref "SV10") (pin "6") (pinfunction "6_6") (pintype "passive"))
      (node (ref "Z") (pin "1") (pinfunction "KL_1") (pintype "passive"))
    )
    (net (code "6") (name "CL1_P") (class "Default")
      (node (ref "CL-1") (pin "2") (pinfunction "2_2") (pintype "passive"))
      (node (ref "X1") (pin "1") (pinfunction "KL_1") (pintype "passive"))
      (node (ref "X1") (pin "2") (pinfunction "KL_2") (pintype "passive"))
    )
    (net (code "7") (name "CL2_P") (class "Default")
      (node (ref "CL-2") (pin "2") (pinfunction "2_2") (pintype "passive"))
      (node (ref "X2") (pin "1") (pinfunction "KL_1") (pintype "passive"))
      (node (ref "X2") (pin "2") (pinfunction "KL_2") (pintype "passive"))
    )
    (net (code "8") (name "CTRL_1") (class "Default")
      (node (ref "IC3") (pin "13") (pinfunction "X0_13") (pintype "bidirectional"))
      (node (ref "R5") (pin "2") (pinfunction "2_2") (pintype "passive"))
    )
    (net (code "9") (name "CTRL_2") (class "Default")
      (node (ref "IC3") (pin "14") (pinfunction "X1_14") (pintype "bidirectional"))
      (node (ref "R7") (pin "2") (pinfunction "2_2") (pintype "passive"))
    )
    (net (code "10") (name "CTRL_3") (class "Default")
      (node (ref "IC3") (pin "15") (pinfunction "X2_15") (pintype "bidirectional"))
      (node (ref "R9") (pin "2") (pinfunction "2_2") (pintype "passive"))
    )
    (net (code "11") (name "CTRL_4") (class "Default")
      (node (ref "IC3") (pin "12") (pinfunction "X3_12") (pintype "bidirectional"))
      (node (ref "R11") (pin "2") (pinfunction "2_2") (pintype "passive"))
    )
    (net (code "12") (name "CTRL_5") (class "Default")
      (node (ref "IC3") (pin "1") (pinfunction "X4_1") (pintype "bidirectional"))
      (node (ref "R13") (pin "2") (pinfunction "2_2") (pintype "passive"))
    )
    (net (code "13") (name "CTRL_6") (class "Default")
      (node (ref "IC3") (pin "5") (pinfunction "X5_5") (pintype "bidirectional"))
      (node (ref "R15") (pin "2") (pinfunction "2_2") (pintype "passive"))
    )
    (net (code "14") (name "CTRL_7") (class "Default")
      (node (ref "IC3") (pin "2") (pinfunction "X6_2") (pintype "bidirectional"))
      (node (ref "R17") (pin "2") (pinfunction "2_2") (pintype "passive"))
    )
    (net (code "15") (name "CTRL_8") (class "Default")
      (node (ref "IC3") (pin "4") (pinfunction "X7_4") (pintype "bidirectional"))
      (node (ref "TP1") (pin "1") (pinfunction "KL_1") (pintype "passive"))
    )
    (net (code "16") (name "DIO_1") (class "Default")
      (node (ref "CON1") (pin "1") (pinfunction "KL_1") (pintype "passive"))
      (node (ref "CON2") (pin "1") (pinfunction "KL_1") (pintype "passive"))
      (node (ref "CON3") (pin "1") (pinfunction "KL_1") (pintype "passive"))
      (node (ref "IC4") (pin "1") (pinfunction "I_1") (pintype "input"))
      (node (ref "R34") (pin "1") (pinfunction "1_1") (pintype "passive"))
    )
    (net (code "17") (name "DIO_2") (class "Default")
      (node (ref "CON1") (pin "2") (pinfunction "KL_2") (pintype "passive"))
      (node (ref "CON2") (pin "2") (pinfunction "KL_2") (pintype "passive"))
      (node (ref "CON3") (pin "2") (pinfunction "KL_2") (pintype "passive"))
      (node (ref "IC4") (pin "3") (pinfunction "I_3") (pintype "input"))
      (node (ref "R35") (pin "1") (pinfunction "1_1") (pintype "passive"))
    )
    (net (code "18") (name "DIO_3") (class "Default")
      (node (ref "CON1") (pin "3") (pinfunction "KL_3") (pintype "passive"))
      (node (ref "CON2") (pin "3") (pinfunction "KL_3") (pintype "passive"))
      (node (ref "CON3") (pin "3") (pinfunction "KL_3") (pintype "passive"))
      (node (ref "IC4") (pin "5") (pinfunction "I_5") (pintype "input"))
      (node (ref "R36") (pin "1") (pinfunction "1_1") (pintype "passive"))
    )
    (net (code "19") (name "DIO_4") (class "Default")
      (node (ref "CON1") (pin "4") (pinfunction "KL_4") (pintype "passive"))
      (node (ref "CON2") (pin "4") (pinfunction "KL_4") (pintype "passive"))
      (node (ref "CON3") (pin "4") (pinfunction "KL_4") (pintype "passive"))
      (node (ref "IC4") (pin "9") (pinfunction "I_9") (pintype "input"))
      (node (ref "R37") (pin "1") (pinfunction "1_1") (pintype "passive"))
    )
    (net (code "20") (name "DIO_5") (class "Default")
      (node (ref "CON1") (pin "6") (pinfunction "KL_6") (pintype "passive"))
    )
    (net (code "21") (name "DIO_6") (class "Default")
      (node (ref "CON1") (pin "7") (pinfunction "KL_7") (pintype "passive"))
    )
    (net (code "22") (name "DIO_7") (class "Default")
      (node (ref "CON1") (pin "8") (pinfunction "KL_8") (pintype "passive"))
    )
    (net (code "23") (name "GND1") (class "Default")
      (node (ref "C1") (pin "2") (pinfunction "-_2") (pintype "passive"))
      (node (ref "C10") (pin "2") (pinfunction "2_2") (pintype "passive"))
      (node (ref "C11") (pin "2") (pinfunction "2_2") (pintype "passive"))
      (node (ref "C2") (pin "2") (pinfunction "-_2") (pintype "passive"))
      (node (ref "C3") (pin "2") (pinfunction "2_2") (pintype "passive"))
      (node (ref "C4") (pin "2") (pinfunction "2_2") (pintype "passive"))
      (node (ref "C7") (pin "2") (pinfunction "-_2") (pintype "passive"))
      (node (ref "C8") (pin "2") (pinfunction "2_2") (pintype "passive"))
      (node (ref "C9") (pin "2") (pinfunction "2_2") (pintype "passive"))
      (node (ref "D12") (pin "A") (pinfunction "A_A") (pintype "passive"))
      (node (ref "IC3") (pin "7") (pinfunction "VEE_7") (pintype "power_in"))
      (node (ref "IC3") (pin "8") (pinfunction "GND_8") (pintype "power_in"))
      (node (ref "IC4") (pin "7") (pinfunction "GND_7") (pintype "power_in"))
      (node (ref "PWR") (pin "C") (pinfunction "C_C") (pintype "passive"))
      (node (ref "PWR-CTRL") (pin "C") (pinfunction "C_C") (pintype "passive"))
      (node (ref "R22") (pin "2") (pinfunction "2_2") (pintype "passive"))
      (node (ref "R24") (pin "2") (pinfunction "2_2") (pintype "passive"))
      (node (ref "R25") (pin "1") (pinfunction "1_1") (pintype "passive"))
      (node (ref "R26") (pin "2") (pinfunction "2_2") (pintype "passive"))
      (node (ref "R27") (pin "1") (pinfunction "1_1") (pintype "passive"))
      (node (ref "R28") (pin "1") (pinfunction "1_1") (pintype "passive"))
      (node (ref "R30") (pin "1") (pinfunction "1_1") (pintype "passive"))
      (node (ref "R31") (pin "1") (pinfunction "1_1") (pintype "passive"))
      (node (ref "R38") (pin "1") (pinfunction "1_1") (pintype "passive"))
      (node (ref "R39") (pin "1") (pinfunction "1_1") (pintype "passive"))
      (node (ref "R41") (pin "1") (pinfunction "1_1") (pintype "passive"))
      (node (ref "R43") (pin "1") (pinfunction "1_1") (pintype "passive"))
      (node (ref "T1") (pin "E") (pinfunction "E_E") (pintype "passive"))
      (node (ref "T2") (pin "E") (pinfunction "E_E") (pintype "passive"))
      (node (ref "T3") (pin "E") (pinfunction "E_E") (pintype "passive"))
      (node (ref "T4") (pin "E") (pinfunction "E_E") (pintype "passive"))
      (node (ref "T5") (pin "E") (pinfunction "E_E") (pintype "passive"))
      (node (ref "T6") (pin "E") (pinfunction "E_E") (pintype "passive"))
      (node (ref "T7") (pin "E") (pinfunction "E_E") (pintype "passive"))
      (node (ref "T8") (pin "C") (pinfunction "C_C") (pintype "passive"))
      (node (ref "X4") (pin "4") (pinfunction "KL_4") (pintype "passive"))
      (node (ref "X4") (pin "5") (pinfunction "KL_5") (pintype "passive"))
    )
    (net (code "24") (name "GNDA") (class "Default")
      (node (ref "C5") (pin "2") (pinfunction "2_2") (pintype "passive"))
      (node (ref "C6") (pin "2") (pinfunction "2_2") (pintype "passive"))
      (node (ref "IC1") (pin "2") (pinfunction "GND_2") (pintype "passive"))
      (node (ref "PWR_ACC") (pin "C") (pinfunction "C_C") (pintype "passive"))
      (node (ref "R24") (pin "1") (pinfunction "1_1") (pintype "passive"))
      (node (ref "R26") (pin "1") (pinfunction "1_1") (pintype "passive"))
      (node (ref "SV10") (pin "1") (pinfunction "1_1") (pintype "passive"))
    )
    (net (code "25") (name "GNDIO") (class "Default")
      (node (ref "CON1") (pin "5") (pinfunction "KL_5") (pintype "passive"))
      (node (ref "CON2") (pin "5") (pinfunction "KL_5") (pintype "passive"))
      (node (ref "CON2") (pin "9") (pinfunction "KL_9") (pintype "passive"))
      (node (ref "CON3") (pin "9") (pinfunction "KL_9") (pintype "passive"))
      (node (ref "R22") (pin "1") (pinfunction "1_1") (pintype "passive"))
      (node (ref "T8") (pin "E") (pinfunction "E_E") (pintype "passive"))
    )
    (net (code "26") (name "Net-(10MEG-PadA)") (class "Default")
      (node (ref "10MEG") (pin "A") (pinfunction "A_A") (pintype "passive"))
      (node (ref "R12") (pin "1") (pinfunction "1_1") (pintype "passive"))
    )
    (net (code "27") (name "Net-(10MEG-PadC)") (class "Default")
      (node (ref "10MEG") (pin "C") (pinfunction "C_C") (pintype "passive"))
      (node (ref "D9") (pin "A") (pinfunction "A_A") (pintype "passive"))
      (node (ref "RLY5") (pin "2") (pinfunction "2_2") (pintype "passive"))
      (node (ref "T5") (pin "C") (pinfunction "C_C") (pintype "passive"))
    )
    (net (code "28") (name "Net-(20MEG-PadA)") (class "Default")
      (node (ref "20MEG") (pin "A") (pinfunction "A_A") (pintype "passive"))
      (node (ref "R14") (pin "1") (pinfunction "1_1") (pintype "passive"))
    )
    (net (code "29") (name "Net-(20MEG-PadC)") (class "Default")
      (node (ref "20MEG") (pin "C") (pinfunction "C_C") (pintype "passive"))
      (node (ref "D10") (pin "A") (pinfunction "A_A") (pintype "passive"))
      (node (ref "RLY6") (pin "2") (pinfunction "2_2") (pintype "passive"))
      (node (ref "T6") (pin "C") (pinfunction "C_C") (pintype "passive"))
    )
    (net (code "30") (name "Net-(B2-Pad1)") (class "Default")
      (node (ref "B2") (pin "1") (pinfunction "1_1") (pintype "bidirectional"))
      (node (ref "RLY1") (pin "4") (pinfunction "4_4") (pintype "passive"))
    )
    (net (code "31") (name "Net-(C7-+)") (class "Default")
      (node (ref "C7") (pin "1") (pinfunction "+_1") (pintype "passive"))
      (node (ref "IC2") (pin "1") (pinfunction "ADJ_1") (pintype "input"))
      (node (ref "R19") (pin "2") (pinfunction "2_2") (pintype "passive"))
      (node (ref "R21") (pin "1") (pinfunction "1_1") (pintype "passive"))
    )
    (net (code "32") (name "Net-(CHARGING-PadA)") (class "Default")
      (node (ref "CHARGING") (pin "A") (pinfunction "A_A") (pintype "passive"))
      (node (ref "R10") (pin "1") (pinfunction "1_1") (pintype "passive"))
    )
    (net (code "33") (name "Net-(CHARGING-PadC)") (class "Default")
      (node (ref "CHARGING") (pin "C") (pinfunction "C_C") (pintype "passive"))
      (node (ref "D8") (pin "A") (pinfunction "A_A") (pintype "passive"))
      (node (ref "RLY4") (pin "2") (pinfunction "2_2") (pintype "passive"))
      (node (ref "T4") (pin "C") (pinfunction "C_C") (pintype "passive"))
    )
    (net (code "34") (name "Net-(CURRENT-PadA)") (class "Default")
      (node (ref "CURRENT") (pin "A") (pinfunction "A_A") (pintype "passive"))
      (node (ref "R6") (pin "1") (pinfunction "1_1") (pintype "passive"))
    )
    (net (code "35") (name "Net-(CURRENT-PadC)") (class "Default")
      (node (ref "CURRENT") (pin "C") (pinfunction "C_C") (pintype "passive"))
      (node (ref "D6") (pin "A") (pinfunction "A_A") (pintype "passive"))
      (node (ref "RLY2") (pin "2") (pinfunction "2_2") (pintype "passive"))
      (node (ref "T2") (pin "C") (pinfunction "C_C") (pintype "passive"))
    )
    (net (code "36") (name "Net-(D1-PadA)") (class "Default")
      (node (ref "D1") (pin "A") (pinfunction "A_A") (pintype "passive"))
      (node (ref "D3") (pin "C") (pinfunction "C_C") (pintype "passive"))
      (node (ref "SW3") (pin "3") (pinfunction "3_3") (pintype "passive"))
    )
    (net (code "37") (name "Net-(D2-PadA)") (class "Default")
      (node (ref "D2") (pin "A") (pinfunction "A_A") (pintype "passive"))
      (node (ref "D4") (pin "C") (pinfunction "C_C") (pintype "passive"))
      (node (ref "SW3") (pin "6") (pinfunction "6_6") (pintype "passive"))
    )
    (net (code "38") (name "Net-(D5-PadA)") (class "Default")
      (node (ref "D5") (pin "A") (pinfunction "A_A") (pintype "passive"))
      (node (ref "RECT") (pin "C") (pinfunction "C_C") (pintype "passive"))
      (node (ref "RLY1") (pin "1") (pinfunction "1_1") (pintype "passive"))
      (node (ref "T1") (pin "C") (pinfunction "C_C") (pintype "passive"))
    )
    (net (code "39") (name "Net-(D7-PadA)") (class "Default")
      (node (ref "D7") (pin "A") (pinfunction "A_A") (pintype "passive"))
      (node (ref "RLY3") (pin "2") (pinfunction "2_2") (pintype "passive"))
      (node (ref "SHORT") (pin "C") (pinfunction "C_C") (pintype "passive"))
      (node (ref "T3") (pin "C") (pinfunction "C_C") (pintype "passive"))
    )
    (net (code "40") (name "Net-(D11-PadA)") (class "Default")
      (node (ref "D11") (pin "A") (pinfunction "A_A") (pintype "passive"))
      (node (ref "EXT-RL") (pin "C") (pinfunction "C_C") (pintype "passive"))
      (node (ref "RLY7") (pin "2") (pinfunction "2_2") (pintype "passive"))
      (node (ref "T7") (pin "C") (pinfunction "C_C") (pintype "passive"))
    )
    (net (code "41") (name "Net-(EXT-RL-PadA)") (class "Default")
      (node (ref "EXT-RL") (pin "A") (pinfunction "A_A") (pintype "passive"))
      (node (ref "R16") (pin "1") (pinfunction "1_1") (pintype "passive"))
    )
    (net (code "42") (name "Net-(IC3A-INH)") (class "Default")
      (node (ref "IC3") (pin "6") (pinfunction "INH_6") (pintype "input"))
      (node (ref "R25") (pin "2") (pinfunction "2_2") (pintype "passive"))
    )
    (net (code "43") (name "Net-(IC4E-I)") (class "Default")
      (node (ref "IC4") (pin "11") (pinfunction "I_11") (pintype "input"))
      (node (ref "R32") (pin "1") (pinfunction "1_1") (pintype "passive"))
    )
    (net (code "44") (name "Net-(IC4E-O)") (class "Default")
      (node (ref "IC4") (pin "10") (pinfunction "O_10") (pintype "output"))
      (node (ref "R38") (pin "2") (pinfunction "2_2") (pintype "passive"))
    )
    (net (code "45") (name "Net-(IC4F-I)") (class "Default")
      (node (ref "IC4") (pin "13") (pinfunction "I_13") (pintype "input"))
      (node (ref "R33") (pin "1") (pinfunction "1_1") (pintype "passive"))
    )
    (net (code "46") (name "Net-(IC4F-O)") (class "Default")
      (node (ref "IC4") (pin "12") (pinfunction "O_12") (pintype "output"))
      (node (ref "R39") (pin "2") (pinfunction "2_2") (pintype "passive"))
    )
    (net (code "47") (name "Net-(PWR-CTRL-PadA)") (class "Default")
      (node (ref "PWR-CTRL") (pin "A") (pinfunction "A_A") (pintype "passive"))
      (node (ref "R23") (pin "1") (pinfunction "1_1") (pintype "passive"))
    )
    (net (code "48") (name "Net-(PWR-PadA)") (class "Default")
      (node (ref "PWR") (pin "A") (pinfunction "A_A") (pintype "passive"))
      (node (ref "R18") (pin "1") (pinfunction "1_1") (pintype "passive"))
    )
    (net (code "49") (name "Net-(PWR_ACC-PadA)") (class "Default")
      (node (ref "PWR_ACC") (pin "A") (pinfunction "A_A") (pintype "passive"))
      (node (ref "R40") (pin "1") (pinfunction "1_1") (pintype "passive"))
    )
    (net (code "50") (name "Net-(R2-Pad2)") (class "Default")
      (node (ref "R2") (pin "2") (pinfunction "2_2") (pintype "passive"))
      (node (ref "R3") (pin "1") (pinfunction "1_1") (pintype "passive"))
    )
    (net (code "51") (name "Net-(R4-Pad1)") (class "Default")
      (node (ref "R4") (pin "1") (pinfunction "1_1") (pintype "passive"))
      (node (ref "RECT") (pin "A") (pinfunction "A_A") (pintype "passive"))
    )
    (net (code "52") (name "Net-(R4-Pad2)") (class "Default")
      (node (ref "R4") (pin "2") (pinfunction "2_2") (pintype "passive"))
      (node (ref "SV3") (pin "1") (pinfunction "1_1") (pintype "passive"))
    )
    (net (code "53") (name "Net-(R5-Pad1)") (class "Default")
      (node (ref "R5") (pin "1") (pinfunction "1_1") (pintype "passive"))
      (node (ref "T1") (pin "B") (pinfunction "B_B") (pintype "passive"))
    )
    (net (code "54") (name "Net-(R6-Pad2)") (class "Default")
      (node (ref "R6") (pin "2") (pinfunction "2_2") (pintype "passive"))
      (node (ref "SV4") (pin "1") (pinfunction "1_1") (pintype "passive"))
    )
    (net (code "55") (name "Net-(R7-Pad1)") (class "Default")
      (node (ref "R7") (pin "1") (pinfunction "1_1") (pintype "passive"))
      (node (ref "T2") (pin "B") (pinfunction "B_B") (pintype "passive"))
    )
    (net (code "56") (name "Net-(R8-Pad1)") (class "Default")
      (node (ref "R8") (pin "1") (pinfunction "1_1") (pintype "passive"))
      (node (ref "SHORT") (pin "A") (pinfunction "A_A") (pintype "passive"))
    )
    (net (code "57") (name "Net-(R8-Pad2)") (class "Default")
      (node (ref "R8") (pin "2") (pinfunction "2_2") (pintype "passive"))
      (node (ref "SV5") (pin "1") (pinfunction "1_1") (pintype "passive"))
    )
    (net (code "58") (name "Net-(R9-Pad1)") (class "Default")
      (node (ref "R9") (pin "1") (pinfunction "1_1") (pintype "passive"))
      (node (ref "T3") (pin "B") (pinfunction "B_B") (pintype "passive"))
    )
    (net (code "59") (name "Net-(R10-Pad2)") (class "Default")
      (node (ref "R10") (pin "2") (pinfunction "2_2") (pintype "passive"))
      (node (ref "SV6") (pin "1") (pinfunction "1_1") (pintype "passive"))
    )
    (net (code "60") (name "Net-(R11-Pad1)") (class "Default")
      (node (ref "R11") (pin "1") (pinfunction "1_1") (pintype "passive"))
      (node (ref "T4") (pin "B") (pinfunction "B_B") (pintype "passive"))
    )
    (net (code "61") (name "Net-(R12-Pad2)") (class "Default")
      (node (ref "R12") (pin "2") (pinfunction "2_2") (pintype "passive"))
      (node (ref "SV7") (pin "1") (pinfunction "1_1") (pintype "passive"))
    )
    (net (code "62") (name "Net-(R13-Pad1)") (class "Default")
      (node (ref "R13") (pin "1") (pinfunction "1_1") (pintype "passive"))
      (node (ref "T5") (pin "B") (pinfunction "B_B") (pintype "passive"))
    )
    (net (code "63") (name "Net-(R14-Pad2)") (class "Default")
      (node (ref "R14") (pin "2") (pinfunction "2_2") (pintype "passive"))
      (node (ref "SV8") (pin "1") (pinfunction "1_1") (pintype "passive"))
    )
    (net (code "64") (name "Net-(R15-Pad1)") (class "Default")
      (node (ref "R15") (pin "1") (pinfunction "1_1") (pintype "passive"))
      (node (ref "T6") (pin "B") (pinfunction "B_B") (pintype "passive"))
    )
    (net (code "65") (name "Net-(R16-Pad2)") (class "Default")
      (node (ref "R16") (pin "2") (pinfunction "2_2") (pintype "passive"))
      (node (ref "SV9") (pin "1") (pinfunction "1_1") (pintype "passive"))
    )
    (net (code "66") (name "Net-(R17-Pad1)") (class "Default")
      (node (ref "R17") (pin "1") (pinfunction "1_1") (pintype "passive"))
      (node (ref "T7") (pin "B") (pinfunction "B_B") (pintype "passive"))
    )
    (net (code "67") (name "Net-(R19-Pad1)") (class "Default")
      (node (ref "R19") (pin "1") (pinfunction "1_1") (pintype "passive"))
      (node (ref "R41") (pin "2") (pinfunction "2_2") (pintype "passive"))
    )
    (net (code "68") (name "Net-(R20-Pad1)") (class "Default")
      (node (ref "R20") (pin "1") (pinfunction "1_1") (pintype "passive"))
      (node (ref "R21") (pin "2") (pinfunction "2_2") (pintype "passive"))
    )
    (net (code "69") (name "Net-(R29-Pad2)") (class "Default")
      (node (ref "R29") (pin "2") (pinfunction "2_2") (pintype "passive"))
      (node (ref "T8") (pin "B") (pinfunction "B_B") (pintype "passive"))
    )
    (net (code "70") (name "Net-(RLY1B-1)") (class "Default")
      (node (ref "B1") (pin "1") (pinfunction "1_1") (pintype "bidirectional"))
      (node (ref "RLY1") (pin "9") (pinfunction "1_9") (pintype "passive"))
    )
    (net (code "71") (name "Net-(RLY2B-1)") (class "Default")
      (node (ref "B4") (pin "1") (pinfunction "1_1") (pintype "bidirectional"))
      (node (ref "B5") (pin "1") (pinfunction "1_1") (pintype "bidirectional"))
      (node (ref "R1") (pin "1") (pinfunction "1_1") (pintype "passive"))
      (node (ref "RLY2") (pin "4") (pinfunction "1_4") (pintype "passive"))
      (node (ref "RLY3") (pin "3") (pinfunction "3_3") (pintype "passive"))
      (node (ref "RLY4") (pin "3") (pinfunction "3_3") (pintype "passive"))
      (node (ref "RLY5") (pin "3") (pinfunction "3_3") (pintype "passive"))
    )
    (net (code "72") (name "Net-(RLY4B-1)") (class "Default")
      (node (ref "CL-1") (pin "1") (pinfunction "1_1") (pintype "passive"))
      (node (ref "CL-2") (pin "1") (pinfunction "1_1") (pintype "passive"))
      (node (ref "RLY4") (pin "4") (pinfunction "1_4") (pintype "passive"))
    )
    (net (code "73") (name "Net-(RLY5B-1)") (class "Default")
      (node (ref "R1") (pin "2") (pinfunction "2_2") (pintype "passive"))
      (node (ref "R2") (pin "1") (pinfunction "1_1") (pintype "passive"))
      (node (ref "RLY5") (pin "4") (pinfunction "1_4") (pintype "passive"))
      (node (ref "RLY6") (pin "3") (pinfunction "3_3") (pintype "passive"))
    )
    (net (code "74") (name "Net-(RLY6B-1)") (class "Default")
      (node (ref "R3") (pin "2") (pinfunction "2_2") (pintype "passive"))
      (node (ref "RLY6") (pin "4") (pinfunction "1_4") (pintype "passive"))
      (node (ref "RLY7") (pin "3") (pinfunction "3_3") (pintype "passive"))
      (node (ref "X3") (pin "1") (pinfunction "KL_1") (pintype "passive"))
    )
    (net (code "75") (name "Net-(SV1-Pad1)") (class "Default")
      (node (ref "SV1") (pin "1") (pinfunction "1_1") (pintype "passive"))
      (node (ref "SW3") (pin "1") (pinfunction "1_1") (pintype "passive"))
    )
    (net (code "76") (name "Net-(SV1-Pad4)") (class "Default")
      (node (ref "SV1") (pin "4") (pinfunction "4_4") (pintype "passive"))
      (node (ref "SW3") (pin "4") (pinfunction "4_4") (pintype "passive"))
    )
    (net (code "77") (name "PWR") (class "Default")
      (node (ref "C1") (pin "1") (pinfunction "+_1") (pintype "passive"))
      (node (ref "D12") (pin "C") (pinfunction "C_C") (pintype "passive"))
      (node (ref "FUSE") (pin "2") (pinfunction "2_2") (pintype "passive"))
      (node (ref "L1") (pin "1") (pinfunction "1_1") (pintype "passive"))
    )
    (net (code "78") (name "PWR_ACC") (class "Default")
      (node (ref "+5V") (pin "1") (pinfunction "KL_1") (pintype "passive"))
      (node (ref "C5") (pin "1") (pinfunction "1_1") (pintype "passive"))
      (node (ref "C6") (pin "1") (pinfunction "1_1") (pintype "passive"))
      (node (ref "IC1") (pin "3") (pinfunction "VO_3") (pintype "passive"))
      (node (ref "SV10") (pin "7") (pinfunction "7_7") (pintype "passive"))
    )
    (net (code "79") (name "PWR_RELAY") (class "Default")
      (node (ref "C8") (pin "1") (pinfunction "1_1") (pintype "passive"))
      (node (ref "C9") (pin "1") (pinfunction "1_1") (pintype "passive"))
      (node (ref "D10") (pin "C") (pinfunction "C_C") (pintype "passive"))
      (node (ref "D11") (pin "C") (pinfunction "C_C") (pintype "passive"))
      (node (ref "D5") (pin "C") (pinfunction "C_C") (pintype "passive"))
      (node (ref "D6") (pin "C") (pinfunction "C_C") (pintype "passive"))
      (node (ref "D7") (pin "C") (pinfunction "C_C") (pintype "passive"))
      (node (ref "D8") (pin "C") (pinfunction "C_C") (pintype "passive"))
      (node (ref "D9") (pin "C") (pinfunction "C_C") (pintype "passive"))
      (node (ref "IC2") (pin "2") (pinfunction "OUT_2") (pintype "passive"))
      (node (ref "R20") (pin "2") (pinfunction "2_2") (pintype "passive"))
      (node (ref "RLY1") (pin "12") (pinfunction "2_12") (pintype "passive"))
      (node (ref "RLY2") (pin "1") (pinfunction "1_1") (pintype "passive"))
      (node (ref "RLY3") (pin "1") (pinfunction "1_1") (pintype "passive"))
      (node (ref "RLY4") (pin "1") (pinfunction "1_1") (pintype "passive"))
      (node (ref "RLY5") (pin "1") (pinfunction "1_1") (pintype "passive"))
      (node (ref "RLY6") (pin "1") (pinfunction "1_1") (pintype "passive"))
      (node (ref "RLY7") (pin "1") (pinfunction "1_1") (pintype "passive"))
      (node (ref "SV3") (pin "2") (pinfunction "2_2") (pintype "passive"))
      (node (ref "SV4") (pin "2") (pinfunction "2_2") (pintype "passive"))
      (node (ref "SV5") (pin "2") (pinfunction "2_2") (pintype "passive"))
      (node (ref "SV6") (pin "2") (pinfunction "2_2") (pintype "passive"))
      (node (ref "SV7") (pin "2") (pinfunction "2_2") (pintype "passive"))
      (node (ref "SV8") (pin "2") (pinfunction "2_2") (pintype "passive"))
      (node (ref "SV9") (pin "2") (pinfunction "2_2") (pintype "passive"))
    )
    (net (code "80") (name "PWR_SUPPLY+") (class "Default")
      (node (ref "FUSE") (pin "1") (pinfunction "1_1") (pintype "passive"))
      (node (ref "X4") (pin "1") (pinfunction "KL_1") (pintype "passive"))
      (node (ref "X4") (pin "2") (pinfunction "KL_2") (pintype "passive"))
    )
    (net (code "81") (name "RCT_IN_1") (class "Default")
      (node (ref "RLY1") (pin "8") (pinfunction "3_8") (pintype "passive"))
      (node (ref "SW3") (pin "2") (pinfunction "2_2") (pintype "passive"))
    )
    (net (code "82") (name "RCT_IN_2") (class "Default")
      (node (ref "RLY1") (pin "5") (pinfunction "6_5") (pintype "passive"))
      (node (ref "SW3") (pin "5") (pinfunction "5_5") (pintype "passive"))
    )
    (net (code "83") (name "RCT_OUT_N") (class "Default")
      (node (ref "B6") (pin "1") (pinfunction "1_1") (pintype "bidirectional"))
      (node (ref "D3") (pin "A") (pinfunction "A_A") (pintype "passive"))
      (node (ref "D4") (pin "A") (pinfunction "A_A") (pintype "passive"))
      (node (ref "RLY1") (pin "3") (pinfunction "5_3") (pintype "passive"))
      (node (ref "RLY3") (pin "4") (pinfunction "1_4") (pintype "passive"))
      (node (ref "RLY7") (pin "4") (pinfunction "1_4") (pintype "passive"))
      (node (ref "SV2") (pin "1") (pinfunction "1_1") (pintype "passive"))
      (node (ref "X1") (pin "4") (pinfunction "KL_4") (pintype "passive"))
      (node (ref "X1") (pin "5") (pinfunction "KL_5") (pintype "passive"))
      (node (ref "X2") (pin "4") (pinfunction "KL_4") (pintype "passive"))
      (node (ref "X2") (pin "5") (pinfunction "KL_5") (pintype "passive"))
      (node (ref "X3") (pin "5") (pinfunction "KL_5") (pintype "passive"))
    )
    (net (code "84") (name "RCT_OUT_P") (class "Default")
      (node (ref "B3") (pin "1") (pinfunction "1_1") (pintype "bidirectional"))
      (node (ref "D1") (pin "C") (pinfunction "C_C") (pintype "passive"))
      (node (ref "D2") (pin "C") (pinfunction "C_C") (pintype "passive"))
      (node (ref "RLY1") (pin "10") (pinfunction "2_10") (pintype "passive"))
      (node (ref "RLY2") (pin "3") (pinfunction "3_3") (pintype "passive"))
      (node (ref "SV2") (pin "4") (pinfunction "4_4") (pintype "passive"))
    )
    (net (code "85") (name "SELF_TEST") (class "Default")
      (node (ref "ST") (pin "1") (pinfunction "KL_1") (pintype "passive"))
      (node (ref "SV10") (pin "5") (pinfunction "5_5") (pintype "passive"))
    )
    (net (code "86") (name "V_IN+") (class "Default")
      (node (ref "C2") (pin "1") (pinfunction "+_1") (pintype "passive"))
      (node (ref "C3") (pin "1") (pinfunction "1_1") (pintype "passive"))
      (node (ref "C4") (pin "1") (pinfunction "1_1") (pintype "passive"))
      (node (ref "IC1") (pin "1") (pinfunction "VI_1") (pintype "input"))
      (node (ref "IC2") (pin "3") (pinfunction "IN_3") (pintype "input"))
      (node (ref "L1") (pin "2") (pinfunction "2_2") (pintype "passive"))
      (node (ref "R18") (pin "2") (pinfunction "2_2") (pintype "passive"))
    )
    (net (code "87") (name "Z_OUT{slash}IN") (class "Default")
      (node (ref "IC3") (pin "3") (pinfunction "X_3") (pintype "bidirectional"))
      (node (ref "R42") (pin "1") (pinfunction "1_1") (pintype "passive"))
      (node (ref "R43") (pin "2") (pinfunction "2_2") (pintype "passive"))
    )
    (net (code "88") (name "unconnected-(CON2F-KL-Pad6)") (class "Default")
      (node (ref "CON2") (pin "6") (pinfunction "KL_6") (pintype "passive"))
    )
    (net (code "89") (name "unconnected-(CON2H-KL-Pad8)") (class "Default")
      (node (ref "CON2") (pin "8") (pinfunction "KL_8") (pintype "passive"))
    )
    (net (code "90") (name "unconnected-(CON3F-KL-Pad6)") (class "Default")
      (node (ref "CON3") (pin "6") (pinfunction "KL_6") (pintype "passive"))
    )
    (net (code "91") (name "unconnected-(CON3G-KL-Pad7)") (class "Default")
      (node (ref "CON3") (pin "7") (pinfunction "KL_7") (pintype "passive"))
    )
    (net (code "92") (name "unconnected-(CON3H-KL-Pad8)") (class "Default")
      (node (ref "CON3") (pin "8") (pinfunction "KL_8") (pintype "passive"))
    )
    (net (code "93") (name "unconnected-(KK1-K-PadA2,2)") (class "Default")
      (node (ref "KK1") (pin "A2,2") (pinfunction "K_A2,2") (pintype "passive"))
    )
    (net (code "94") (name "unconnected-(KK1-K-PadB2,2)") (class "Default")
      (node (ref "KK1") (pin "B2,2") (pinfunction "K_B2,2") (pintype "passive"))
    )
    (net (code "95") (name "unconnected-(SV1-Pad2)") (class "Default")
      (node (ref "SV1") (pin "2") (pinfunction "2_2") (pintype "passive"))
    )
    (net (code "96") (name "unconnected-(SV1-Pad3)") (class "Default")
      (node (ref "SV1") (pin "3") (pinfunction "3_3") (pintype "passive"))
    )
    (net (code "97") (name "unconnected-(SV2-Pad2)") (class "Default")
      (node (ref "SV2") (pin "2") (pinfunction "2_2") (pintype "passive"))
    )
    (net (code "98") (name "unconnected-(SV2-Pad3)") (class "Default")
      (node (ref "SV2") (pin "3") (pinfunction "3_3") (pintype "passive"))
    )
    (net (code "99") (name "unconnected-(SV3-Pad3)") (class "Default")
      (node (ref "SV3") (pin "3") (pinfunction "3_3") (pintype "passive"))
    )
    (net (code "100") (name "unconnected-(SV4-Pad3)") (class "Default")
      (node (ref "SV4") (pin "3") (pinfunction "3_3") (pintype "passive"))
    )
    (net (code "101") (name "unconnected-(SV5-Pad3)") (class "Default")
      (node (ref "SV5") (pin "3") (pinfunction "3_3") (pintype "passive"))
    )
    (net (code "102") (name "unconnected-(SV6-Pad3)") (class "Default")
      (node (ref "SV6") (pin "3") (pinfunction "3_3") (pintype "passive"))
    )
    (net (code "103") (name "unconnected-(SV7-Pad3)") (class "Default")
      (node (ref "SV7") (pin "3") (pinfunction "3_3") (pintype "passive"))
    )
    (net (code "104") (name "unconnected-(SV8-Pad3)") (class "Default")
      (node (ref "SV8") (pin "3") (pinfunction "3_3") (pintype "passive"))
    )
    (net (code "105") (name "unconnected-(SV9-Pad3)") (class "Default")
      (node (ref "SV9") (pin "3") (pinfunction "3_3") (pintype "passive"))
    )
    (net (code "106") (name "unconnected-(SV10-Pad3)") (class "Default")
      (node (ref "SV10") (pin "3") (pinfunction "3_3") (pintype "passive"))
    )
    (net (code "107") (name "unconnected-(X1C-KL-Pad3)") (class "Default")
      (node (ref "X1") (pin "3") (pinfunction "KL_3") (pintype "passive"))
    )
    (net (code "108") (name "unconnected-(X2C-KL-Pad3)") (class "Default")
      (node (ref "X2") (pin "3") (pinfunction "KL_3") (pintype "passive"))
    )
    (net (code "109") (name "unconnected-(X3B-KL-Pad2)") (class "Default")
      (node (ref "X3") (pin "2") (pinfunction "KL_2") (pintype "passive"))
    )
    (net (code "110") (name "unconnected-(X3C-KL-Pad3)") (class "Default")
      (node (ref "X3") (pin "3") (pinfunction "KL_3") (pintype "passive"))
    )
    (net (code "111") (name "unconnected-(X3D-KL-Pad4)") (class "Default")
      (node (ref "X3") (pin "4") (pinfunction "KL_4") (pintype "passive"))
    )
    (net (code "112") (name "unconnected-(X4C-KL-Pad3)") (class "Default")
      (node (ref "X4") (pin "3") (pinfunction "KL_3") (pintype "passive"))
    )
    (net (code "113") (name "~{DIO_1}") (class "Default")
      (node (ref "IC3") (pin "11") (pinfunction "A_11") (pintype "input"))
      (node (ref "IC4") (pin "2") (pinfunction "O_2") (pintype "output"))
      (node (ref "R27") (pin "2") (pinfunction "2_2") (pintype "passive"))
    )
    (net (code "114") (name "~{DIO_2}") (class "Default")
      (node (ref "IC3") (pin "10") (pinfunction "B_10") (pintype "input"))
      (node (ref "IC4") (pin "4") (pinfunction "O_4") (pintype "output"))
      (node (ref "R28") (pin "2") (pinfunction "2_2") (pintype "passive"))
    )
    (net (code "115") (name "~{DIO_3}") (class "Default")
      (node (ref "IC3") (pin "9") (pinfunction "C_9") (pintype "input"))
      (node (ref "IC4") (pin "6") (pinfunction "O_6") (pintype "output"))
      (node (ref "R30") (pin "2") (pinfunction "2_2") (pintype "passive"))
    )
    (net (code "116") (name "~{DIO_4}") (class "Default")
      (node (ref "IC4") (pin "8") (pinfunction "O_8") (pintype "output"))
      (node (ref "R31") (pin "2") (pinfunction "2_2") (pintype "passive"))
    )
  )
)
